# PFC_Method_V1_1.net
KiCad netlist of a schematic drawn in EAGLE
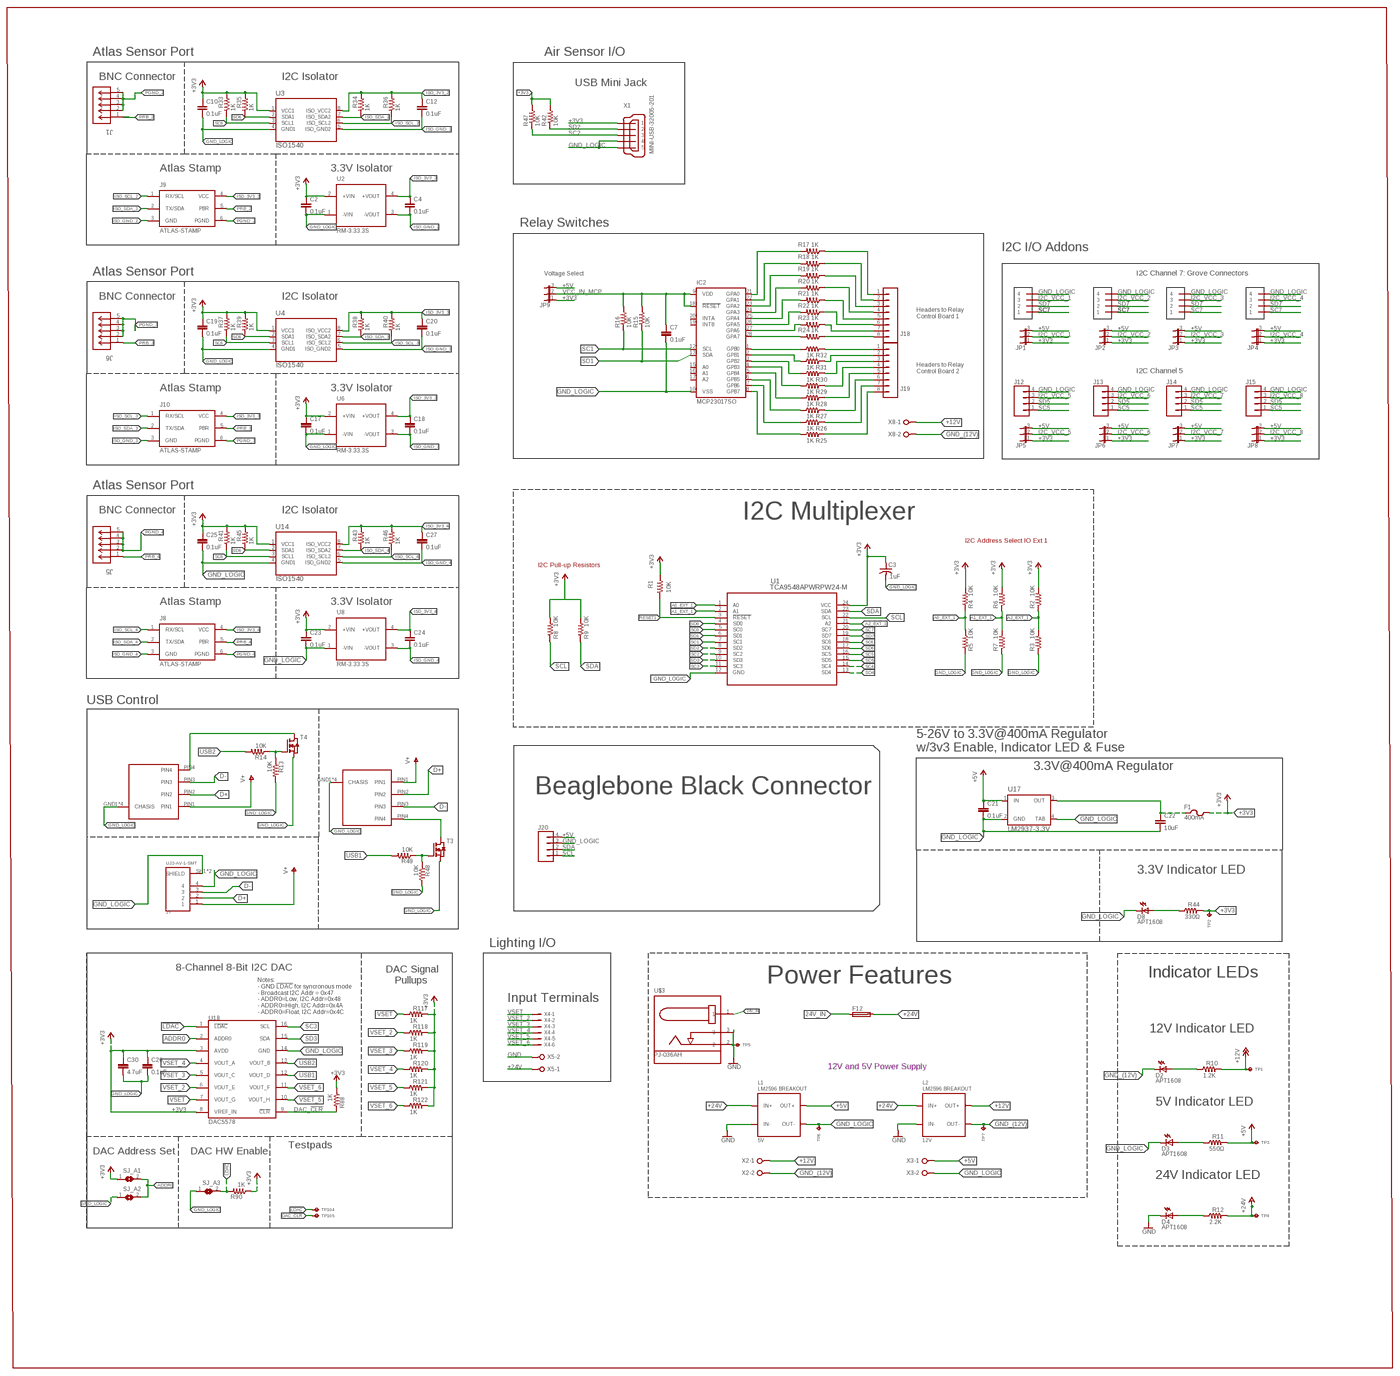
[diagram p0: schematic, sheet 1, overview]
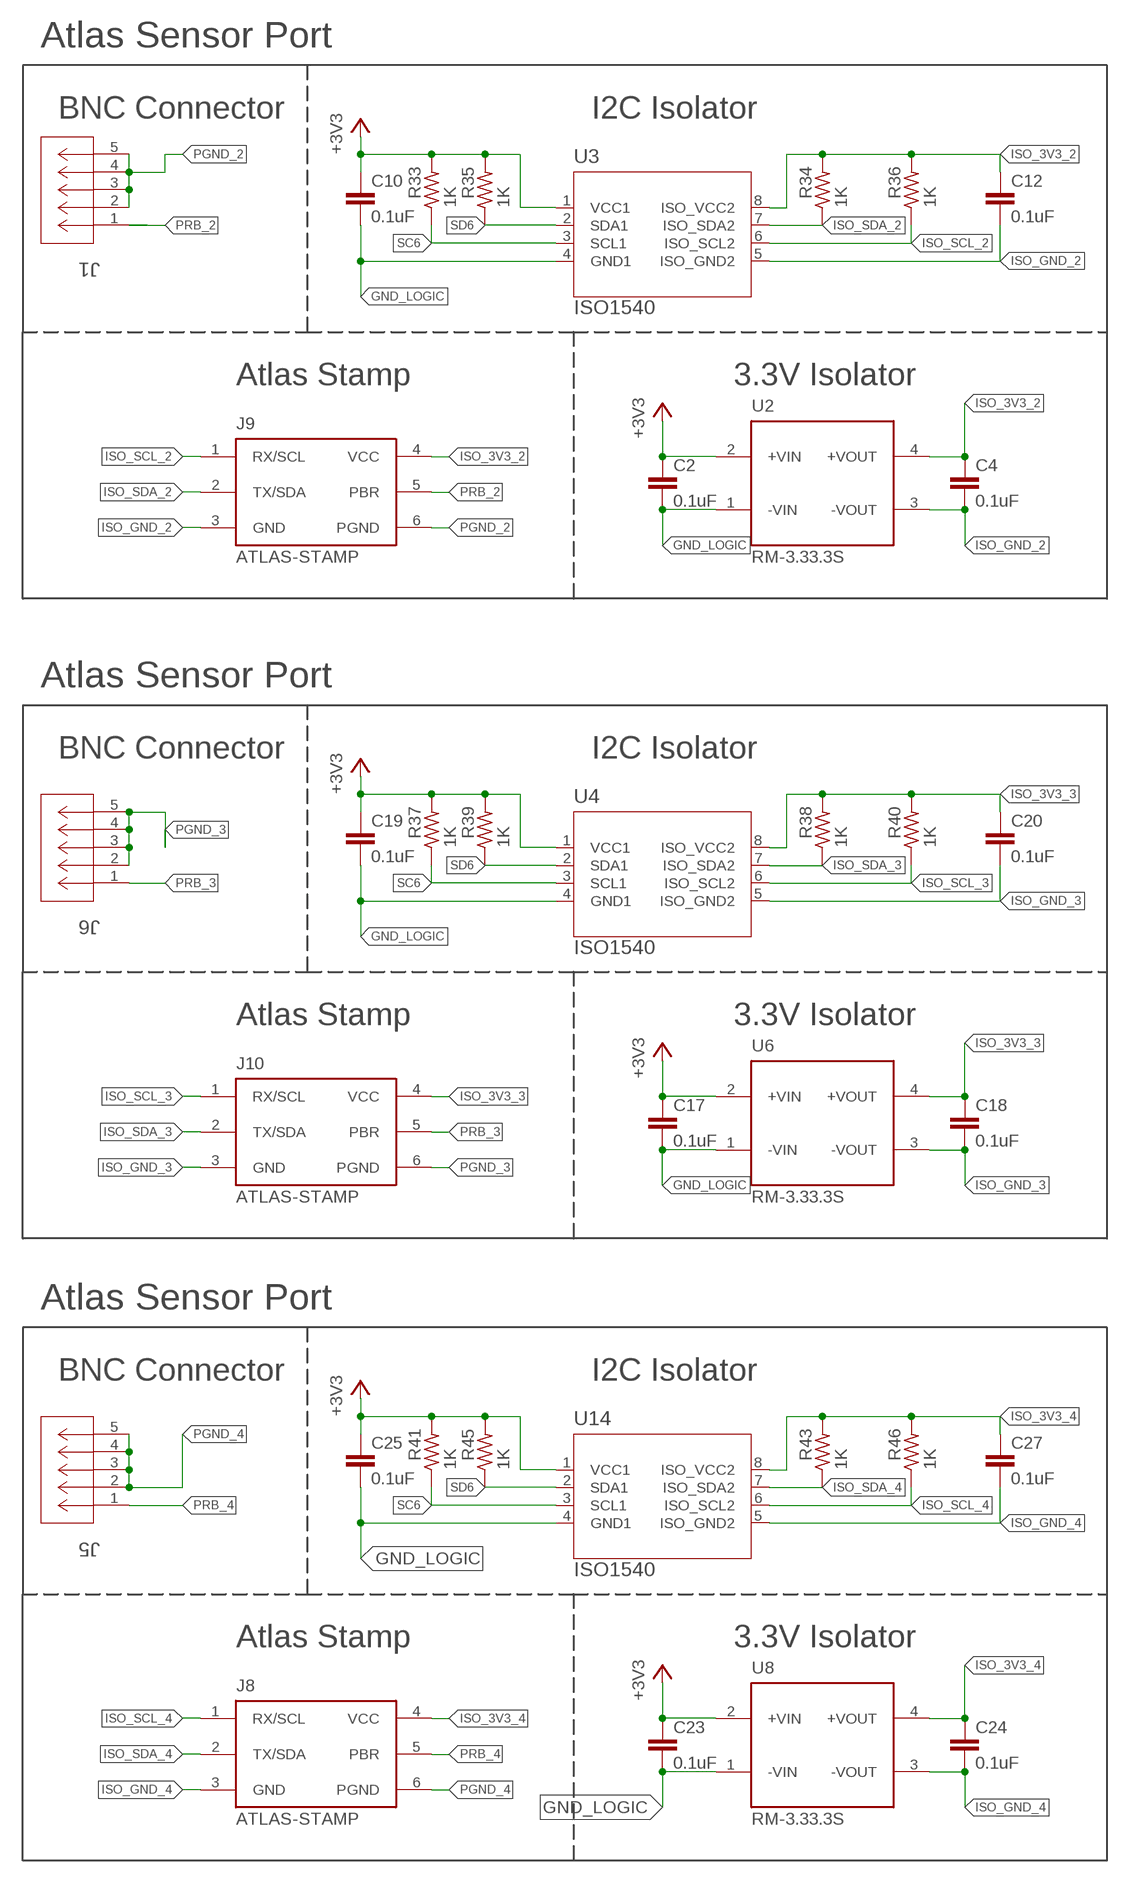
[diagram p1: schematic, sheet 1, part 1 of 4]
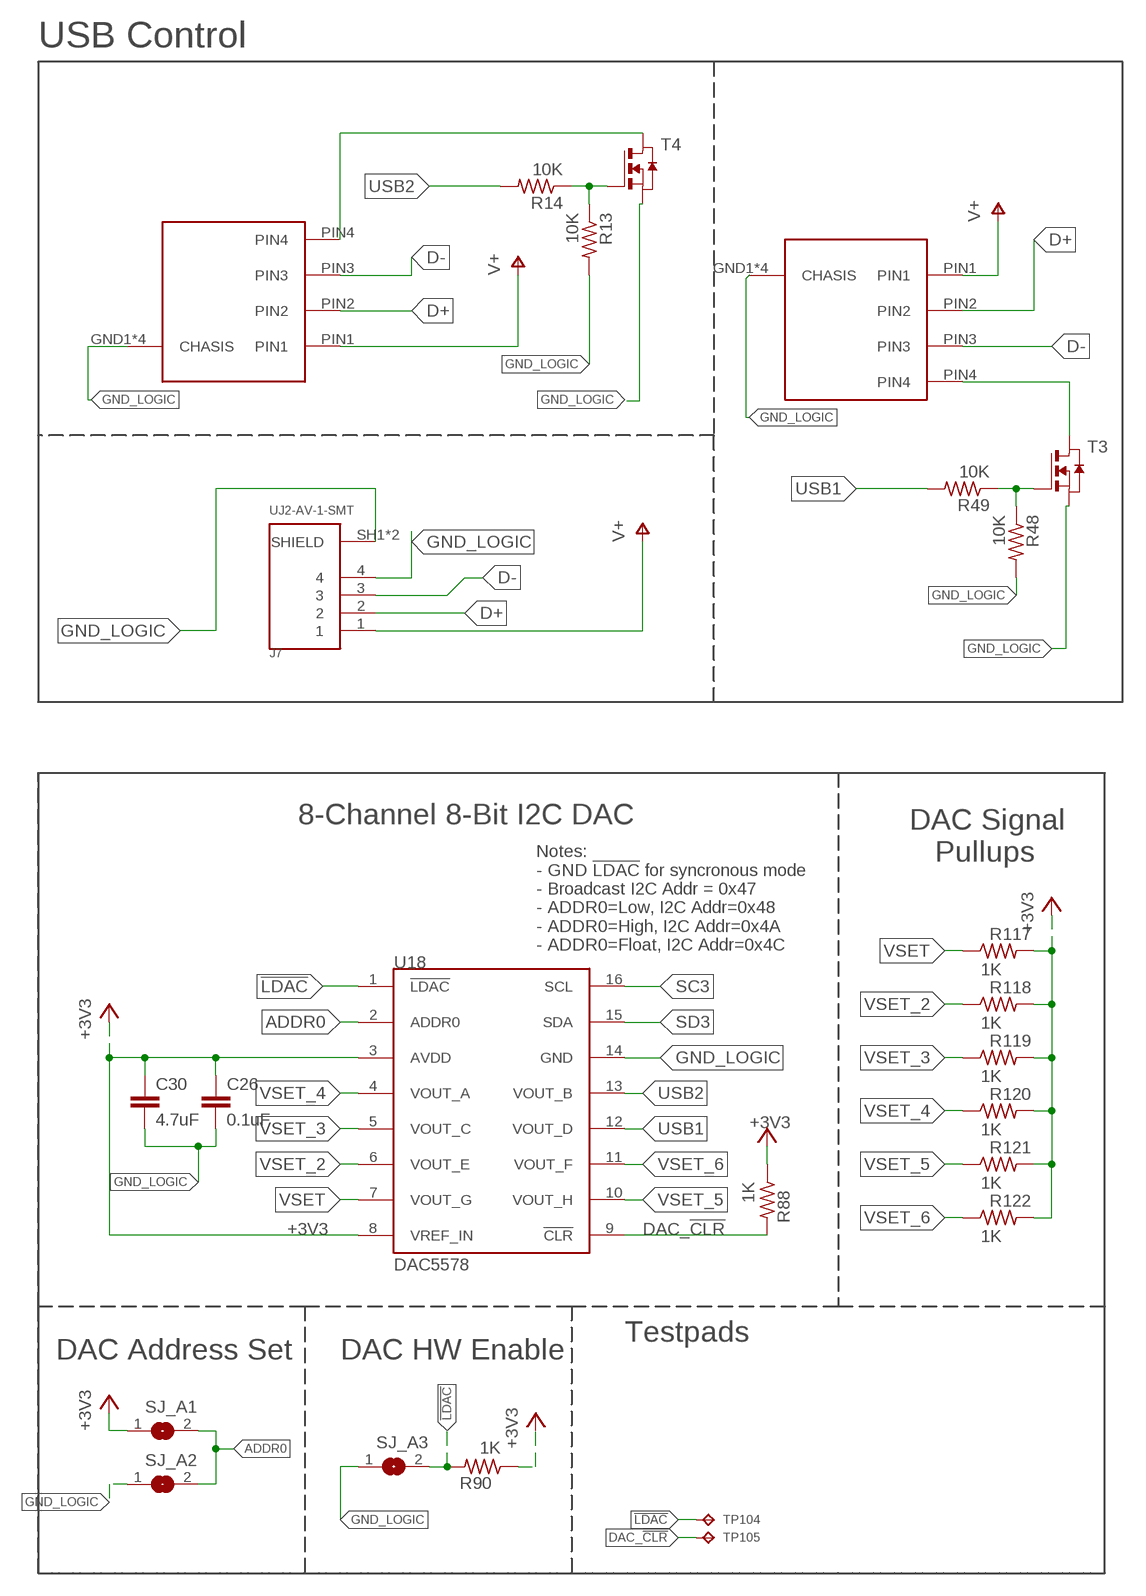
[diagram p2: schematic, sheet 1, part 2 of 4]
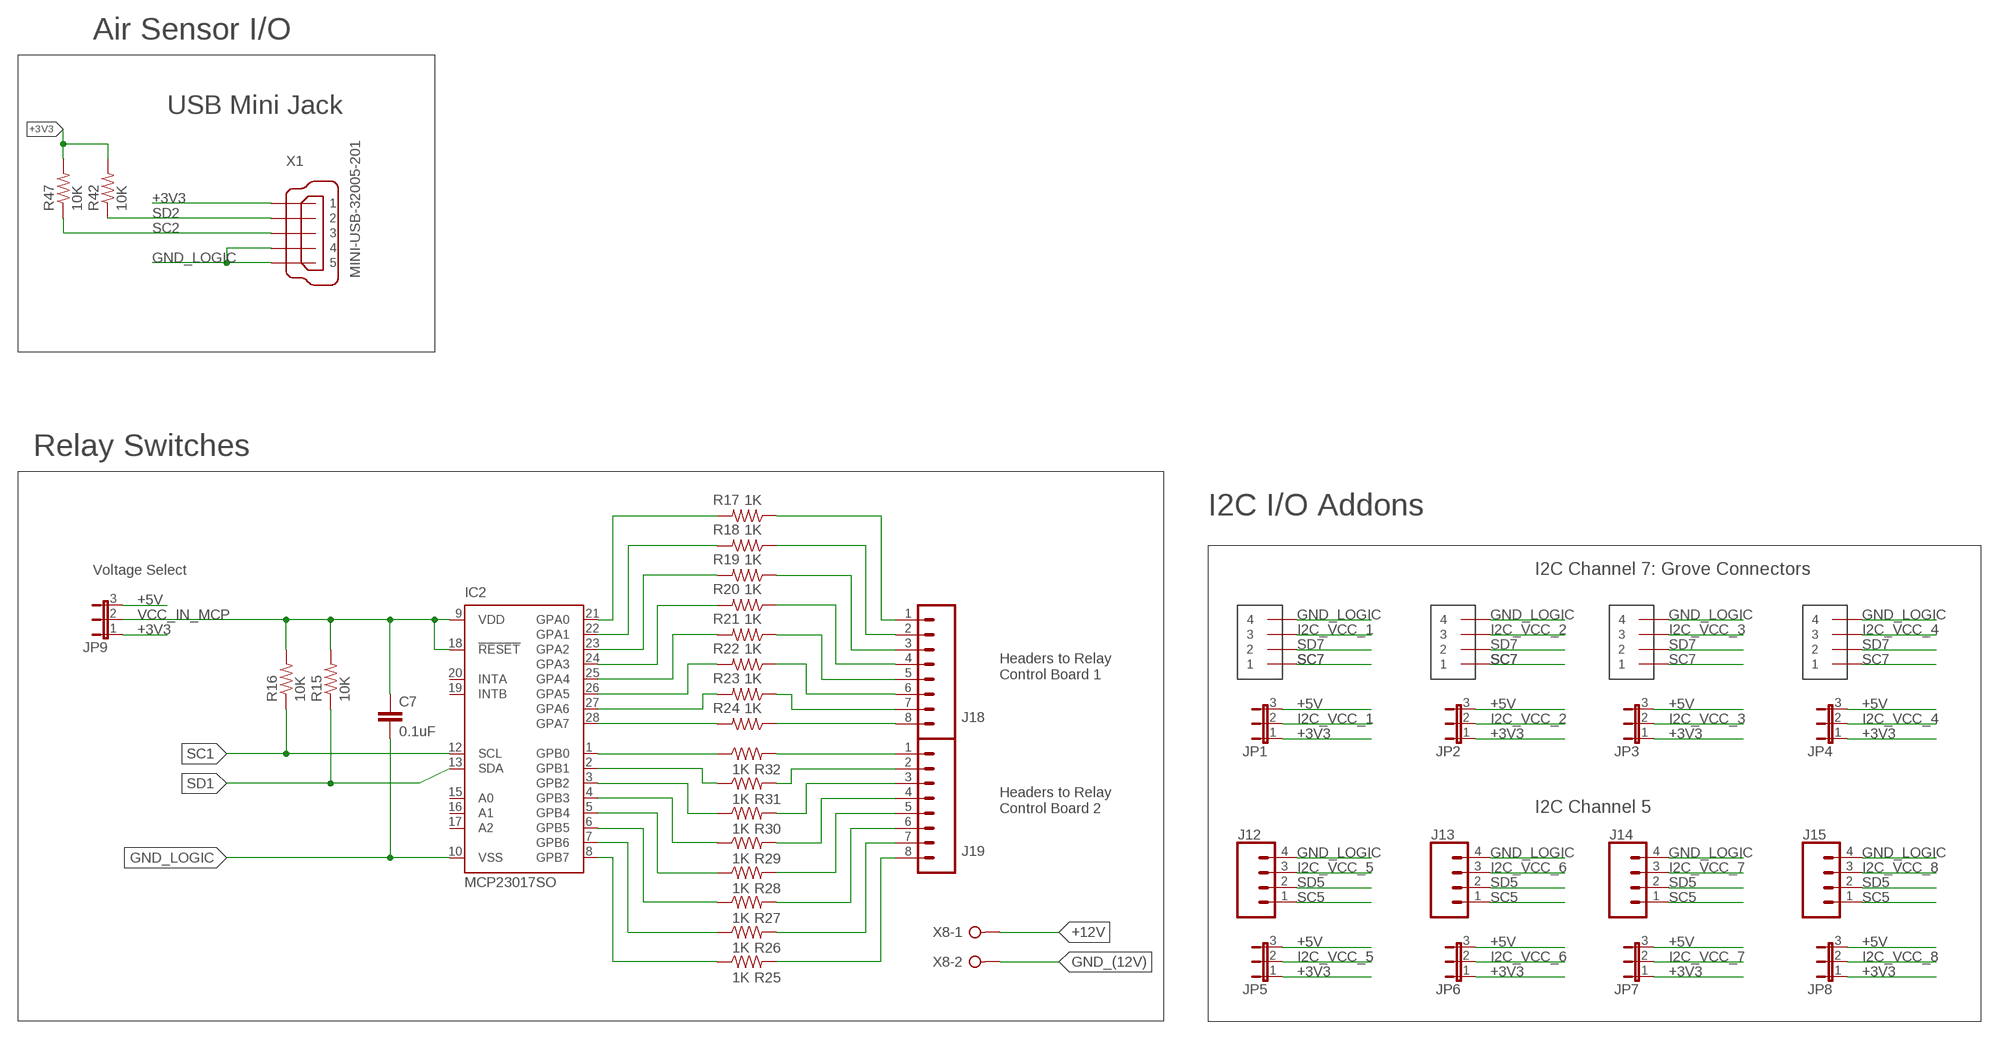
[diagram p3: schematic, sheet 1, part 3 of 4]
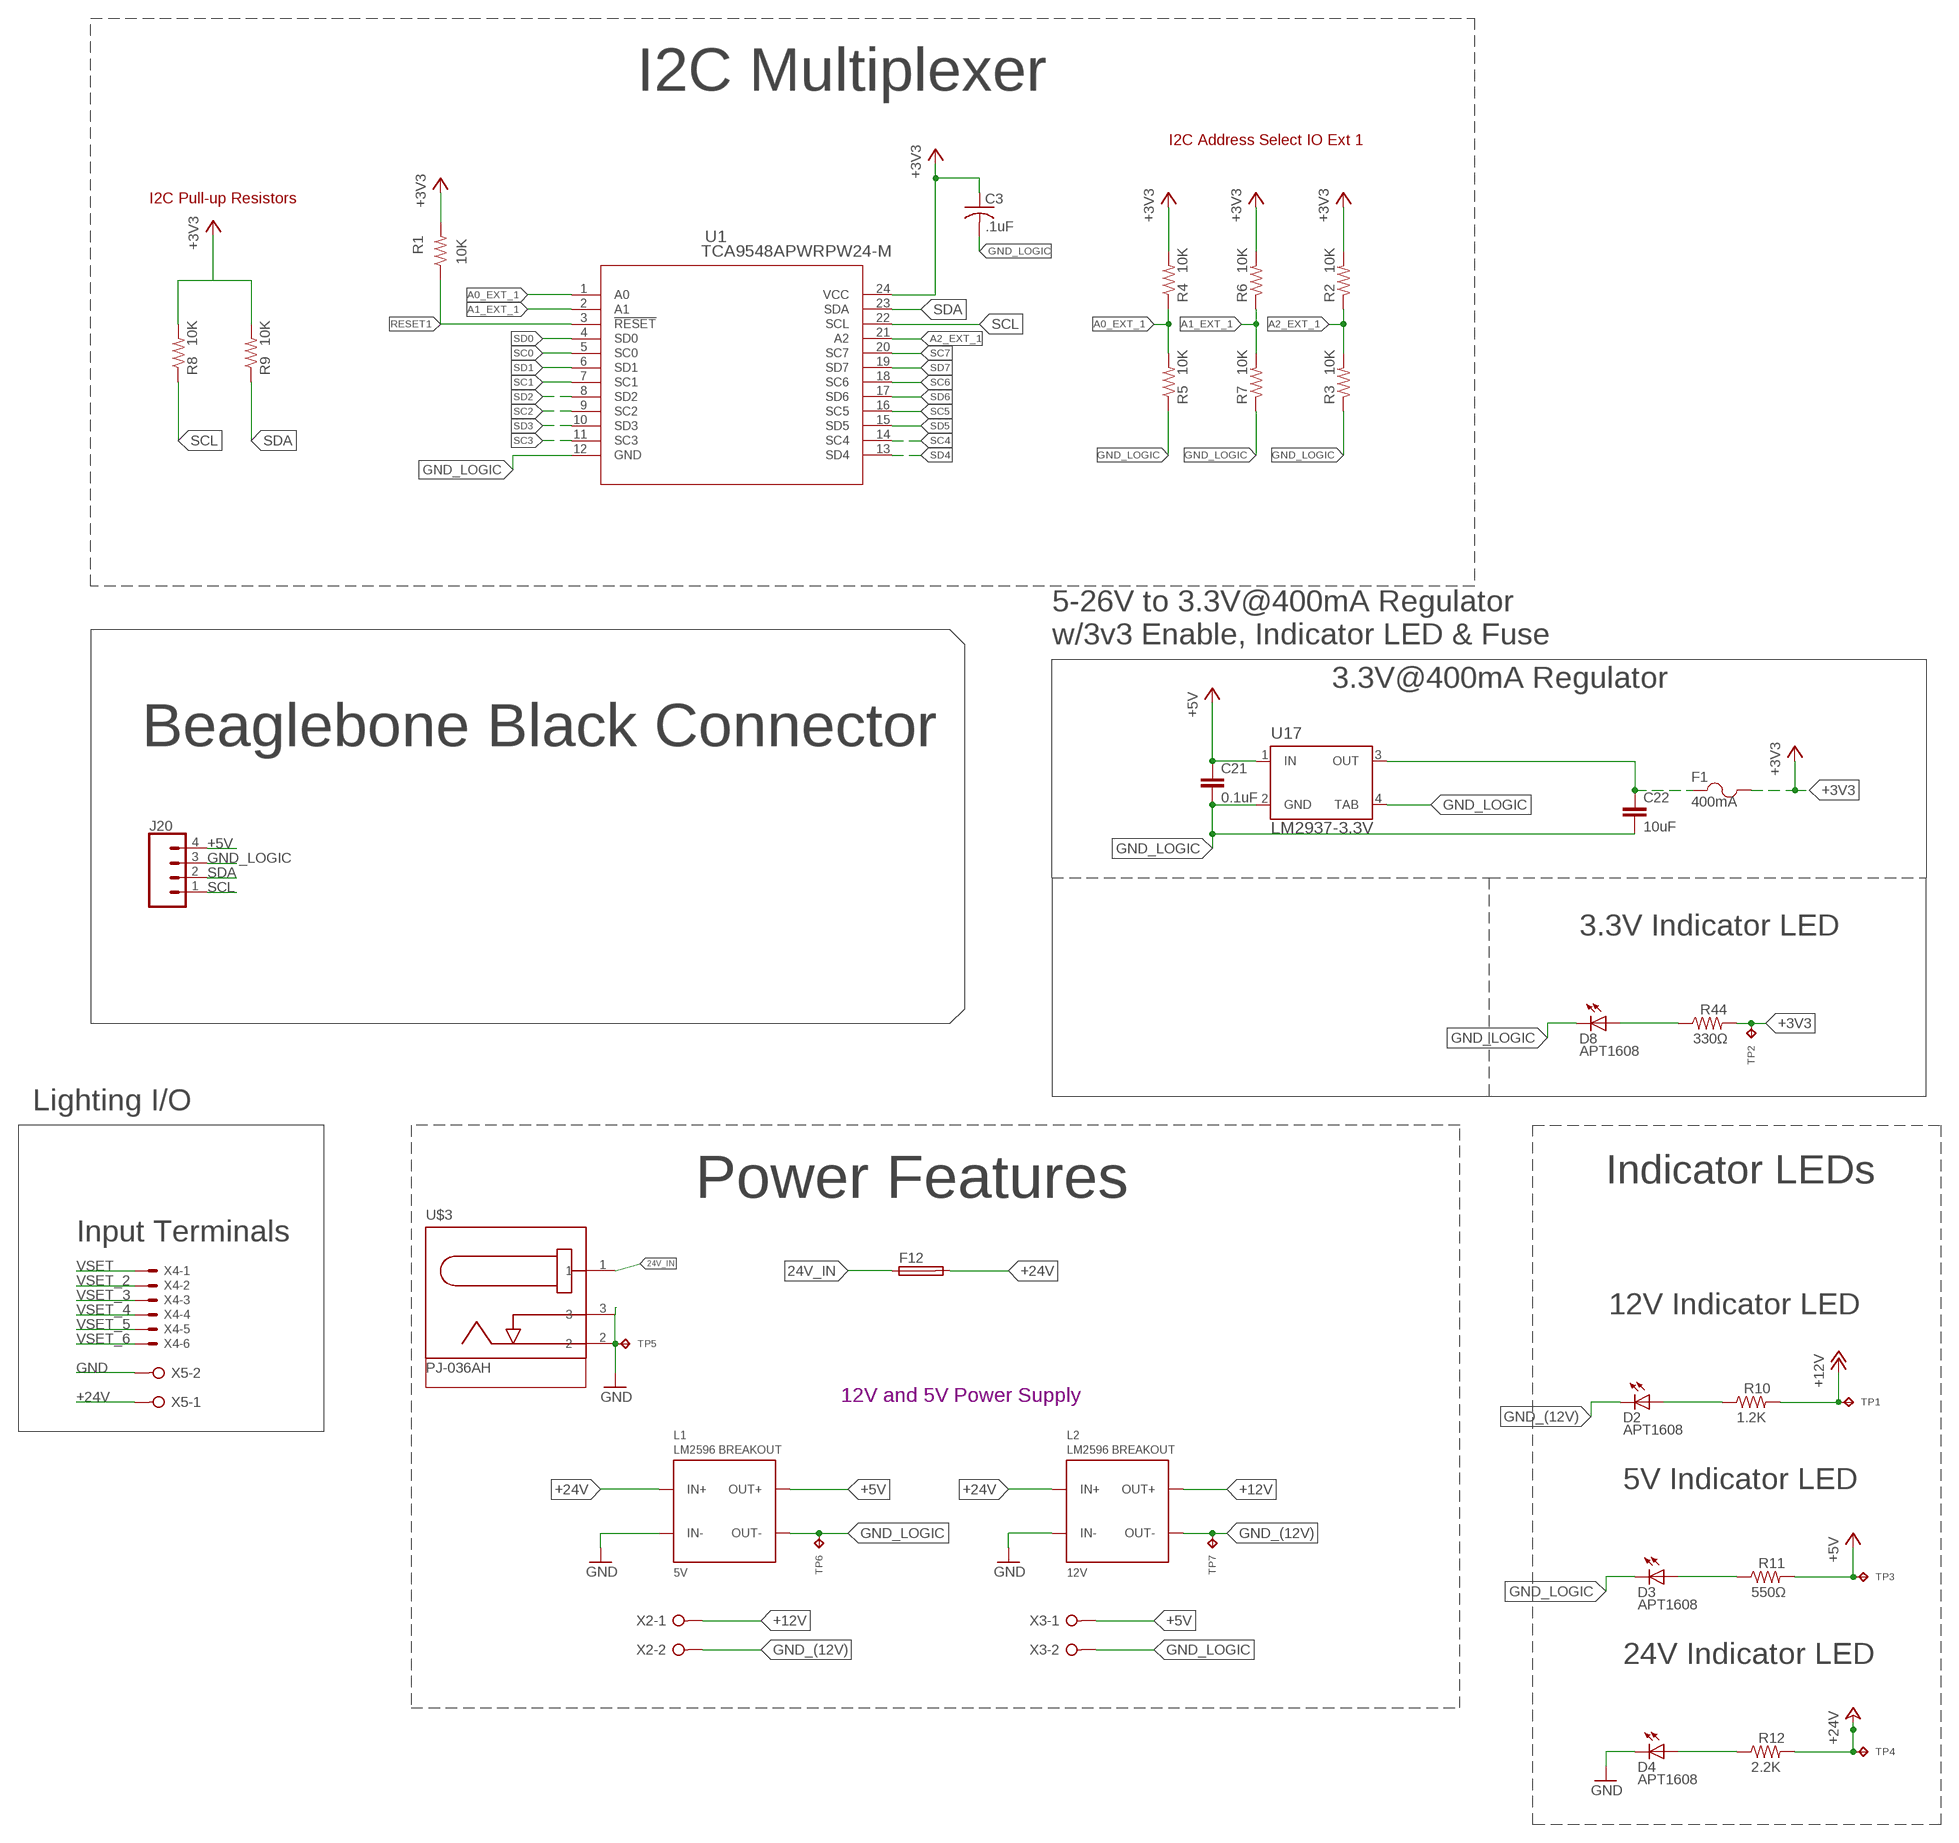
[diagram p4: schematic, sheet 1, part 4 of 4]

(export (version "E")
  (design (tool "Eeschema 10.0.6"))
  (components
    (comp (ref "C2")
      (value "0.1uF")
      (footprint "eagle-import:C0603")
      (fields (field (name "MANUFACTURER") "Kemet") (field (name "MPN") "C0603C104K5RACTU"))
      (libsource (lib "eagle-import") (part "0.1UF-C0603C104K5RACTU"))
    )
    (comp (ref "C3")
      (value ".1uF")
      (footprint "eagle-import:C0603@1")
      (libsource (lib "eagle-import") (part "C-USC0603"))
    )
    (comp (ref "C4")
      (value "0.1uF")
      (footprint "eagle-import:C0603")
      (fields (field (name "MANUFACTURER") "Kemet") (field (name "MPN") "C0603C104K5RACTU"))
      (libsource (lib "eagle-import") (part "0.1UF-C0603C104K5RACTU"))
    )
    (comp (ref "C7")
      (value "0.1uF")
      (footprint "eagle-import:C0603")
      (fields (field (name "MANUFACTURER") "Kemet") (field (name "MPN") "C0603C104K5RACTU"))
      (libsource (lib "eagle-import") (part "0.1UF-C0603C104K5RACTU"))
    )
    (comp (ref "C10")
      (value "0.1uF")
      (footprint "eagle-import:C0603")
      (fields (field (name "MANUFACTURER") "Kemet") (field (name "MPN") "C0603C104K5RACTU"))
      (libsource (lib "eagle-import") (part "0.1UF-C0603C104K5RACTU"))
    )
    (comp (ref "C12")
      (value "0.1uF")
      (footprint "eagle-import:C0603")
      (fields (field (name "MANUFACTURER") "Kemet") (field (name "MPN") "C0603C104K5RACTU"))
      (libsource (lib "eagle-import") (part "0.1UF-C0603C104K5RACTU"))
    )
    (comp (ref "C17")
      (value "0.1uF")
      (footprint "eagle-import:C0603")
      (fields (field (name "MANUFACTURER") "Kemet") (field (name "MPN") "C0603C104K5RACTU"))
      (libsource (lib "eagle-import") (part "0.1UF-C0603C104K5RACTU"))
    )
    (comp (ref "C18")
      (value "0.1uF")
      (footprint "eagle-import:C0603")
      (fields (field (name "MANUFACTURER") "Kemet") (field (name "MPN") "C0603C104K5RACTU"))
      (libsource (lib "eagle-import") (part "0.1UF-C0603C104K5RACTU"))
    )
    (comp (ref "C19")
      (value "0.1uF")
      (footprint "eagle-import:C0603")
      (fields (field (name "MANUFACTURER") "Kemet") (field (name "MPN") "C0603C104K5RACTU"))
      (libsource (lib "eagle-import") (part "0.1UF-C0603C104K5RACTU"))
    )
    (comp (ref "C20")
      (value "0.1uF")
      (footprint "eagle-import:C0603")
      (fields (field (name "MANUFACTURER") "Kemet") (field (name "MPN") "C0603C104K5RACTU"))
      (libsource (lib "eagle-import") (part "0.1UF-C0603C104K5RACTU"))
    )
    (comp (ref "C21")
      (value "0.1uF")
      (footprint "eagle-import:C0603")
      (fields (field (name "MANUFACTURER") "Kemet") (field (name "MPN") "C0603C104K5RACTU"))
      (libsource (lib "eagle-import") (part "0.1UF-C0603C104K5RACTU"))
    )
    (comp (ref "C22")
      (value "10uF")
      (footprint "eagle-import:C0805")
      (fields (field (name "MANUFACTURER") "Taiyo Yuden") (field (name "MPN") "GMK212BBJ106KG-T"))
      (libsource (lib "eagle-import") (part "10UF-GMK212BBJ106KG-T"))
    )
    (comp (ref "C23")
      (value "0.1uF")
      (footprint "eagle-import:C0603")
      (fields (field (name "MANUFACTURER") "Kemet") (field (name "MPN") "C0603C104K5RACTU"))
      (libsource (lib "eagle-import") (part "0.1UF-C0603C104K5RACTU"))
    )
    (comp (ref "C24")
      (value "0.1uF")
      (footprint "eagle-import:C0603")
      (fields (field (name "MANUFACTURER") "Kemet") (field (name "MPN") "C0603C104K5RACTU"))
      (libsource (lib "eagle-import") (part "0.1UF-C0603C104K5RACTU"))
    )
    (comp (ref "C25")
      (value "0.1uF")
      (footprint "eagle-import:C0603")
      (fields (field (name "MANUFACTURER") "Kemet") (field (name "MPN") "C0603C104K5RACTU"))
      (libsource (lib "eagle-import") (part "0.1UF-C0603C104K5RACTU"))
    )
    (comp (ref "C26")
      (value "0.1uF")
      (footprint "eagle-import:C0603")
      (fields (field (name "MANUFACTURER") "Kemet") (field (name "MPN") "C0603C104K5RACTU"))
      (libsource (lib "eagle-import") (part "0.1UF-C0603C104K5RACTU"))
    )
    (comp (ref "C27")
      (value "0.1uF")
      (footprint "eagle-import:C0603")
      (fields (field (name "MANUFACTURER") "Kemet") (field (name "MPN") "C0603C104K5RACTU"))
      (libsource (lib "eagle-import") (part "0.1UF-C0603C104K5RACTU"))
    )
    (comp (ref "C30")
      (value "4.7uF")
      (footprint "eagle-import:C0805")
      (fields (field (name "MANUFACTURER") "Samsung") (field (name "MPN") "CL21A475KBQNNNE"))
      (libsource (lib "eagle-import") (part "4.7UF-CL21A475KBQNNNE"))
    )
    (comp (ref "D2")
      (value "APT1608")
      (footprint "eagle-import:CHIPLED_0603")
      (fields (field (name "MANUFACTURER") "Kingbright") (field (name "MPN") "APT1608CGCK"))
      (libsource (lib "eagle-import") (part "APT1608CGCK"))
    )
    (comp (ref "D3")
      (value "APT1608")
      (footprint "eagle-import:CHIPLED_0603")
      (fields (field (name "MANUFACTURER") "Kingbright") (field (name "MPN") "APT1608CGCK"))
      (libsource (lib "eagle-import") (part "APT1608CGCK"))
    )
    (comp (ref "D4")
      (value "APT1608")
      (footprint "eagle-import:CHIPLED_0603")
      (fields (field (name "MANUFACTURER") "Kingbright") (field (name "MPN") "APT1608CGCK"))
      (libsource (lib "eagle-import") (part "APT1608CGCK"))
    )
    (comp (ref "D8")
      (value "APT1608")
      (footprint "eagle-import:CHIPLED_0603")
      (fields (field (name "MANUFACTURER") "Kingbright") (field (name "MPN") "APT1608CGCK"))
      (libsource (lib "eagle-import") (part "APT1608CGCK"))
    )
    (comp (ref "F1")
      (value "400mA")
      (footprint "eagle-import:0603")
      (fields (field (name "MANUFACTURER") "Littlefuse Inc.") (field (name "MPN") "0448.400MR"))
      (libsource (lib "eagle-import") (part "0438.375WR"))
    )
    (comp (ref "F12")
      (value "GSH15")
      (footprint "eagle-import:GSH15")
      (fields (field (name "MPN") "64900001039"))
      (libsource (lib "eagle-import") (part "GSH15"))
    )
    (comp (ref "IC2")
      (value "MCP23017SO")
      (footprint "eagle-import:SO28W")
      (fields (field (name "MF") "MICROCHIP") (field (name "MPN") "MCP23017-E/SO"))
      (libsource (lib "eagle-import") (part "MCP23017SO"))
    )
    (comp (ref "J1")
      (value "5-1634503-1")
      (footprint "eagle-import:CONN5_5-1634503-1")
      (fields (field (name "MANUFACTURER_PART_NUMBER") "516345031"))
      (libsource (lib "eagle-import") (part "5-1634503-1"))
    )
    (comp (ref "J2")
      (value "GROVE_4PIN_CONNECTOR")
      (footprint "eagle-import:GROVE_4PIN_CONNECTOR")
      (libsource (lib "eagle-import") (part "GROVE_4PIN_CONNECTOR"))
    )
    (comp (ref "J3")
      (value "GROVE_4PIN_CONNECTOR")
      (footprint "eagle-import:GROVE_4PIN_CONNECTOR")
      (libsource (lib "eagle-import") (part "GROVE_4PIN_CONNECTOR"))
    )
    (comp (ref "J5")
      (value "5-1634503-1")
      (footprint "eagle-import:CONN5_5-1634503-1")
      (fields (field (name "MANUFACTURER_PART_NUMBER") "516345031"))
      (libsource (lib "eagle-import") (part "5-1634503-1"))
    )
    (comp (ref "J6")
      (value "5-1634503-1")
      (footprint "eagle-import:CONN5_5-1634503-1")
      (fields (field (name "MANUFACTURER_PART_NUMBER") "516345031"))
      (libsource (lib "eagle-import") (part "5-1634503-1"))
    )
    (comp (ref "J7")
      (value "UJ2-AV-1-SMT")
      (footprint "eagle-import:CUI_UJ2-AV-1-SMT")
      (fields (field (name "MANUFACTURER") "CUI INC"))
      (libsource (lib "eagle-import") (part "UJ2-AV-1-SMT"))
    )
    (comp (ref "J8")
      (value "ATLAS-STAMP")
      (footprint "eagle-import:ATLAS-STAMP")
      (libsource (lib "eagle-import") (part "ATLAS-STAMP"))
    )
    (comp (ref "J9")
      (value "ATLAS-STAMP")
      (footprint "eagle-import:ATLAS-STAMP")
      (libsource (lib "eagle-import") (part "ATLAS-STAMP"))
    )
    (comp (ref "J10")
      (value "ATLAS-STAMP")
      (footprint "eagle-import:ATLAS-STAMP")
      (libsource (lib "eagle-import") (part "ATLAS-STAMP"))
    )
    (comp (ref "J12")
      (value "CONN_04")
      (footprint "eagle-import:1X04")
      (libsource (lib "eagle-import") (part "CONN_04"))
    )
    (comp (ref "J13")
      (value "CONN_04")
      (footprint "eagle-import:1X04")
      (libsource (lib "eagle-import") (part "CONN_04"))
    )
    (comp (ref "J14")
      (value "CONN_04")
      (footprint "eagle-import:1X04")
      (libsource (lib "eagle-import") (part "CONN_04"))
    )
    (comp (ref "J15")
      (value "CONN_04")
      (footprint "eagle-import:1X04")
      (libsource (lib "eagle-import") (part "CONN_04"))
    )
    (comp (ref "J16")
      (value "GROVE_4PIN_CONNECTOR")
      (footprint "eagle-import:GROVE_4PIN_CONNECTOR")
      (libsource (lib "eagle-import") (part "GROVE_4PIN_CONNECTOR"))
    )
    (comp (ref "J17")
      (value "GROVE_4PIN_CONNECTOR")
      (footprint "eagle-import:GROVE_4PIN_CONNECTOR")
      (libsource (lib "eagle-import") (part "GROVE_4PIN_CONNECTOR"))
    )
    (comp (ref "J18")
      (value "CONN_08\"")
      (footprint "eagle-import:1X08")
      (libsource (lib "eagle-import") (part "CONN_08{dblquote}"))
    )
    (comp (ref "J19")
      (value "CONN_08\"")
      (footprint "eagle-import:1X08")
      (libsource (lib "eagle-import") (part "CONN_08{dblquote}"))
    )
    (comp (ref "J20")
      (value "CONN_04")
      (footprint "eagle-import:1X04")
      (libsource (lib "eagle-import") (part "CONN_04"))
    )
    (comp (ref "JP1")
      (value "JP2E")
      (footprint "eagle-import:JP2")
      (libsource (lib "eagle-import") (part "JP2E"))
    )
    (comp (ref "JP2")
      (value "JP2E")
      (footprint "eagle-import:JP2")
      (libsource (lib "eagle-import") (part "JP2E"))
    )
    (comp (ref "JP3")
      (value "JP2E")
      (footprint "eagle-import:JP2")
      (libsource (lib "eagle-import") (part "JP2E"))
    )
    (comp (ref "JP4")
      (value "JP2E")
      (footprint "eagle-import:JP2")
      (libsource (lib "eagle-import") (part "JP2E"))
    )
    (comp (ref "JP5")
      (value "JP2E")
      (footprint "eagle-import:JP2")
      (libsource (lib "eagle-import") (part "JP2E"))
    )
    (comp (ref "JP6")
      (value "JP2E")
      (footprint "eagle-import:JP2")
      (libsource (lib "eagle-import") (part "JP2E"))
    )
    (comp (ref "JP7")
      (value "JP2E")
      (footprint "eagle-import:JP2")
      (libsource (lib "eagle-import") (part "JP2E"))
    )
    (comp (ref "JP8")
      (value "JP2E")
      (footprint "eagle-import:JP2")
      (libsource (lib "eagle-import") (part "JP2E"))
    )
    (comp (ref "JP9")
      (value "JP2E")
      (footprint "eagle-import:JP2")
      (libsource (lib "eagle-import") (part "JP2E"))
    )
    (comp (ref "L1")
      (value "5V")
      (footprint "eagle-import:LM2596")
      (libsource (lib "eagle-import") (part "LM2596_BREAKOUT"))
    )
    (comp (ref "L2")
      (value "12V")
      (footprint "eagle-import:LM2596")
      (libsource (lib "eagle-import") (part "LM2596_BREAKOUT"))
    )
    (comp (ref "R1")
      (value "10K")
      (footprint "eagle-import:R0603")
      (libsource (lib "eagle-import") (part "R-US_R0603"))
    )
    (comp (ref "R2")
      (value "10K")
      (footprint "eagle-import:0603-RES")
      (libsource (lib "eagle-import") (part "10KOHM-1/10W-1%(0603)0603"))
    )
    (comp (ref "R3")
      (value "10K")
      (footprint "eagle-import:0603-RES")
      (libsource (lib "eagle-import") (part "10KOHM-1/10W-1%(0603)0603"))
    )
    (comp (ref "R4")
      (value "10K")
      (footprint "eagle-import:0603-RES")
      (libsource (lib "eagle-import") (part "10KOHM-1/10W-1%(0603)0603"))
    )
    (comp (ref "R5")
      (value "10K")
      (footprint "eagle-import:0603-RES")
      (libsource (lib "eagle-import") (part "10KOHM-1/10W-1%(0603)0603"))
    )
    (comp (ref "R6")
      (value "10K")
      (footprint "eagle-import:0603-RES")
      (libsource (lib "eagle-import") (part "10KOHM-1/10W-1%(0603)0603"))
    )
    (comp (ref "R7")
      (value "10K")
      (footprint "eagle-import:0603-RES")
      (libsource (lib "eagle-import") (part "10KOHM-1/10W-1%(0603)0603"))
    )
    (comp (ref "R8")
      (value "10K")
      (footprint "eagle-import:0603-RES")
      (libsource (lib "eagle-import") (part "10KOHM-1/10W-1%(0603)0603"))
    )
    (comp (ref "R9")
      (value "10K")
      (footprint "eagle-import:0603-RES")
      (libsource (lib "eagle-import") (part "10KOHM-1/10W-1%(0603)0603"))
    )
    (comp (ref "R10")
      (value "1.2K")
      (footprint "eagle-import:RC0603N")
      (fields (field (name "MANUFACTURER") "Yageo") (field (name "MPN") "RC0603JR-07100RL"))
      (libsource (lib "eagle-import") (part "100OHM-RC0603JR-07100RL"))
    )
    (comp (ref "R11")
      (value "550Ω")
      (footprint "eagle-import:RC0603N")
      (fields (field (name "MANUFACTURER") "Yageo") (field (name "MPN") "RC0603JR-07100RL"))
      (libsource (lib "eagle-import") (part "100OHM-RC0603JR-07100RL"))
    )
    (comp (ref "R12")
      (value "2.2K")
      (footprint "eagle-import:RC0603N")
      (fields (field (name "MANUFACTURER") "Yageo") (field (name "MPN") "RC0603JR-07100RL"))
      (libsource (lib "eagle-import") (part "100OHM-RC0603JR-07100RL"))
    )
    (comp (ref "R13")
      (value "10K")
      (footprint "eagle-import:R0805W")
      (libsource (lib "eagle-import") (part "R-US_R0805W"))
    )
    (comp (ref "R14")
      (value "10K")
      (footprint "eagle-import:R0805W")
      (libsource (lib "eagle-import") (part "R-US_R0805W"))
    )
    (comp (ref "R15")
      (value "10K")
      (footprint "eagle-import:R0603")
      (libsource (lib "eagle-import") (part "R-US_R0603"))
    )
    (comp (ref "R16")
      (value "10K")
      (footprint "eagle-import:R0603")
      (libsource (lib "eagle-import") (part "R-US_R0603"))
    )
    (comp (ref "R17")
      (value "1K")
      (footprint "eagle-import:RC0603N")
      (fields (field (name "MANUFACTURER") "Panasonic") (field (name "MPN") "P20283CT-ND"))
      (libsource (lib "eagle-import") (part "1K-ERJ-PB3D1001V"))
    )
    (comp (ref "R18")
      (value "1K")
      (footprint "eagle-import:RC0603N")
      (fields (field (name "MANUFACTURER") "Panasonic") (field (name "MPN") "P20283CT-ND"))
      (libsource (lib "eagle-import") (part "1K-ERJ-PB3D1001V"))
    )
    (comp (ref "R19")
      (value "1K")
      (footprint "eagle-import:RC0603N")
      (fields (field (name "MANUFACTURER") "Panasonic") (field (name "MPN") "P20283CT-ND"))
      (libsource (lib "eagle-import") (part "1K-ERJ-PB3D1001V"))
    )
    (comp (ref "R20")
      (value "1K")
      (footprint "eagle-import:RC0603N")
      (fields (field (name "MANUFACTURER") "Panasonic") (field (name "MPN") "P20283CT-ND"))
      (libsource (lib "eagle-import") (part "1K-ERJ-PB3D1001V"))
    )
    (comp (ref "R21")
      (value "1K")
      (footprint "eagle-import:RC0603N")
      (fields (field (name "MANUFACTURER") "Panasonic") (field (name "MPN") "P20283CT-ND"))
      (libsource (lib "eagle-import") (part "1K-ERJ-PB3D1001V"))
    )
    (comp (ref "R22")
      (value "1K")
      (footprint "eagle-import:RC0603N")
      (fields (field (name "MANUFACTURER") "Panasonic") (field (name "MPN") "P20283CT-ND"))
      (libsource (lib "eagle-import") (part "1K-ERJ-PB3D1001V"))
    )
    (comp (ref "R23")
      (value "1K")
      (footprint "eagle-import:RC0603N")
      (fields (field (name "MANUFACTURER") "Panasonic") (field (name "MPN") "P20283CT-ND"))
      (libsource (lib "eagle-import") (part "1K-ERJ-PB3D1001V"))
    )
    (comp (ref "R24")
      (value "1K")
      (footprint "eagle-import:RC0603N")
      (fields (field (name "MANUFACTURER") "Panasonic") (field (name "MPN") "P20283CT-ND"))
      (libsource (lib "eagle-import") (part "1K-ERJ-PB3D1001V"))
    )
    (comp (ref "R25")
      (value "1K")
      (footprint "eagle-import:RC0603N")
      (fields (field (name "MANUFACTURER") "Panasonic") (field (name "MPN") "P20283CT-ND"))
      (libsource (lib "eagle-import") (part "1K-ERJ-PB3D1001V"))
    )
    (comp (ref "R26")
      (value "1K")
      (footprint "eagle-import:RC0603N")
      (fields (field (name "MANUFACTURER") "Panasonic") (field (name "MPN") "P20283CT-ND"))
      (libsource (lib "eagle-import") (part "1K-ERJ-PB3D1001V"))
    )
    (comp (ref "R27")
      (value "1K")
      (footprint "eagle-import:RC0603N")
      (fields (field (name "MANUFACTURER") "Panasonic") (field (name "MPN") "P20283CT-ND"))
      (libsource (lib "eagle-import") (part "1K-ERJ-PB3D1001V"))
    )
    (comp (ref "R28")
      (value "1K")
      (footprint "eagle-import:RC0603N")
      (fields (field (name "MANUFACTURER") "Panasonic") (field (name "MPN") "P20283CT-ND"))
      (libsource (lib "eagle-import") (part "1K-ERJ-PB3D1001V"))
    )
    (comp (ref "R29")
      (value "1K")
      (footprint "eagle-import:RC0603N")
      (fields (field (name "MANUFACTURER") "Panasonic") (field (name "MPN") "P20283CT-ND"))
      (libsource (lib "eagle-import") (part "1K-ERJ-PB3D1001V"))
    )
    (comp (ref "R30")
      (value "1K")
      (footprint "eagle-import:RC0603N")
      (fields (field (name "MANUFACTURER") "Panasonic") (field (name "MPN") "P20283CT-ND"))
      (libsource (lib "eagle-import") (part "1K-ERJ-PB3D1001V"))
    )
    (comp (ref "R31")
      (value "1K")
      (footprint "eagle-import:RC0603N")
      (fields (field (name "MANUFACTURER") "Panasonic") (field (name "MPN") "P20283CT-ND"))
      (libsource (lib "eagle-import") (part "1K-ERJ-PB3D1001V"))
    )
    (comp (ref "R32")
      (value "1K")
      (footprint "eagle-import:RC0603N")
      (fields (field (name "MANUFACTURER") "Panasonic") (field (name "MPN") "P20283CT-ND"))
      (libsource (lib "eagle-import") (part "1K-ERJ-PB3D1001V"))
    )
    (comp (ref "R33")
      (value "1K")
      (footprint "eagle-import:RC0603N")
      (fields (field (name "MANUFACTURER") "Panasonic") (field (name "MPN") "P20283CT-ND"))
      (libsource (lib "eagle-import") (part "1K-ERJ-PB3D1001V"))
    )
    (comp (ref "R34")
      (value "1K")
      (footprint "eagle-import:RC0603N")
      (fields (field (name "MANUFACTURER") "Panasonic") (field (name "MPN") "P20283CT-ND"))
      (libsource (lib "eagle-import") (part "1K-ERJ-PB3D1001V"))
    )
    (comp (ref "R35")
      (value "1K")
      (footprint "eagle-import:RC0603N")
      (fields (field (name "MANUFACTURER") "Panasonic") (field (name "MPN") "P20283CT-ND"))
      (libsource (lib "eagle-import") (part "1K-ERJ-PB3D1001V"))
    )
    (comp (ref "R36")
      (value "1K")
      (footprint "eagle-import:RC0603N")
      (fields (field (name "MANUFACTURER") "Panasonic") (field (name "MPN") "P20283CT-ND"))
      (libsource (lib "eagle-import") (part "1K-ERJ-PB3D1001V"))
    )
    (comp (ref "R37")
      (value "1K")
      (footprint "eagle-import:RC0603N")
      (fields (field (name "MANUFACTURER") "Panasonic") (field (name "MPN") "P20283CT-ND"))
      (libsource (lib "eagle-import") (part "1K-ERJ-PB3D1001V"))
    )
    (comp (ref "R38")
      (value "1K")
      (footprint "eagle-import:RC0603N")
      (fields (field (name "MANUFACTURER") "Panasonic") (field (name "MPN") "P20283CT-ND"))
      (libsource (lib "eagle-import") (part "1K-ERJ-PB3D1001V"))
    )
    (comp (ref "R39")
      (value "1K")
      (footprint "eagle-import:RC0603N")
      (fields (field (name "MANUFACTURER") "Panasonic") (field (name "MPN") "P20283CT-ND"))
      (libsource (lib "eagle-import") (part "1K-ERJ-PB3D1001V"))
    )
    (comp (ref "R40")
      (value "1K")
      (footprint "eagle-import:RC0603N")
      (fields (field (name "MANUFACTURER") "Panasonic") (field (name "MPN") "P20283CT-ND"))
      (libsource (lib "eagle-import") (part "1K-ERJ-PB3D1001V"))
    )
    (comp (ref "R41")
      (value "1K")
      (footprint "eagle-import:RC0603N")
      (fields (field (name "MANUFACTURER") "Panasonic") (field (name "MPN") "P20283CT-ND"))
      (libsource (lib "eagle-import") (part "1K-ERJ-PB3D1001V"))
    )
    (comp (ref "R42")
      (value "10K")
      (footprint "eagle-import:R0603")
      (libsource (lib "eagle-import") (part "R-US_R0603"))
    )
    (comp (ref "R43")
      (value "1K")
      (footprint "eagle-import:RC0603N")
      (fields (field (name "MANUFACTURER") "Panasonic") (field (name "MPN") "P20283CT-ND"))
      (libsource (lib "eagle-import") (part "1K-ERJ-PB3D1001V"))
    )
    (comp (ref "R44")
      (value "330Ω")
      (footprint "eagle-import:RC0603N")
      (fields (field (name "MANUFACTURER") "Yageo") (field (name "MPN") "RC0603JR-07100RL"))
      (libsource (lib "eagle-import") (part "100OHM-RC0603JR-07100RL"))
    )
    (comp (ref "R45")
      (value "1K")
      (footprint "eagle-import:RC0603N")
      (fields (field (name "MANUFACTURER") "Panasonic") (field (name "MPN") "P20283CT-ND"))
      (libsource (lib "eagle-import") (part "1K-ERJ-PB3D1001V"))
    )
    (comp (ref "R46")
      (value "1K")
      (footprint "eagle-import:RC0603N")
      (fields (field (name "MANUFACTURER") "Panasonic") (field (name "MPN") "P20283CT-ND"))
      (libsource (lib "eagle-import") (part "1K-ERJ-PB3D1001V"))
    )
    (comp (ref "R47")
      (value "10K")
      (footprint "eagle-import:R0603")
      (libsource (lib "eagle-import") (part "R-US_R0603"))
    )
    (comp (ref "R48")
      (value "10K")
      (footprint "eagle-import:R0805W")
      (libsource (lib "eagle-import") (part "R-US_R0805W"))
    )
    (comp (ref "R49")
      (value "10K")
      (footprint "eagle-import:R0805W")
      (libsource (lib "eagle-import") (part "R-US_R0805W"))
    )
    (comp (ref "R88")
      (value "1K")
      (footprint "eagle-import:RC0603N")
      (fields (field (name "MANUFACTURER") "Panasonic") (field (name "MPN") "P20283CT-ND"))
      (libsource (lib "eagle-import") (part "1K-ERJ-PB3D1001V"))
    )
    (comp (ref "R90")
      (value "1K")
      (footprint "eagle-import:RC0603N")
      (fields (field (name "MANUFACTURER") "Panasonic") (field (name "MPN") "P20283CT-ND"))
      (libsource (lib "eagle-import") (part "1K-ERJ-PB3D1001V"))
    )
    (comp (ref "R117")
      (value "1K")
      (footprint "eagle-import:RC0603N")
      (fields (field (name "MANUFACTURER") "Panasonic") (field (name "MPN") "P20283CT-ND"))
      (libsource (lib "eagle-import") (part "1K-ERJ-PB3D1001V"))
    )
    (comp (ref "R118")
      (value "1K")
      (footprint "eagle-import:RC0603N")
      (fields (field (name "MANUFACTURER") "Panasonic") (field (name "MPN") "P20283CT-ND"))
      (libsource (lib "eagle-import") (part "1K-ERJ-PB3D1001V"))
    )
    (comp (ref "R119")
      (value "1K")
      (footprint "eagle-import:RC0603N")
      (fields (field (name "MANUFACTURER") "Panasonic") (field (name "MPN") "P20283CT-ND"))
      (libsource (lib "eagle-import") (part "1K-ERJ-PB3D1001V"))
    )
    (comp (ref "R120")
      (value "1K")
      (footprint "eagle-import:RC0603N")
      (fields (field (name "MANUFACTURER") "Panasonic") (field (name "MPN") "P20283CT-ND"))
      (libsource (lib "eagle-import") (part "1K-ERJ-PB3D1001V"))
    )
    (comp (ref "R121")
      (value "1K")
      (footprint "eagle-import:RC0603N")
      (fields (field (name "MANUFACTURER") "Panasonic") (field (name "MPN") "P20283CT-ND"))
      (libsource (lib "eagle-import") (part "1K-ERJ-PB3D1001V"))
    )
    (comp (ref "R122")
      (value "1K")
      (footprint "eagle-import:RC0603N")
      (fields (field (name "MANUFACTURER") "Panasonic") (field (name "MPN") "P20283CT-ND"))
      (libsource (lib "eagle-import") (part "1K-ERJ-PB3D1001V"))
    )
    (comp (ref "SJ_A1")
      (value "SOLDERJUMPERREFLOW_NOPASTE")
      (footprint "eagle-import:SJ1")
      (libsource (lib "eagle-import") (part "SOLDERJUMPERREFLOW_NOPASTE"))
    )
    (comp (ref "SJ_A2")
      (value "SOLDERJUMPERREFLOW_NOPASTE")
      (footprint "eagle-import:SJ1")
      (libsource (lib "eagle-import") (part "SOLDERJUMPERREFLOW_NOPASTE"))
    )
    (comp (ref "SJ_A3")
      (value "SOLDERJUMPERREFLOW_NOPASTE")
      (footprint "eagle-import:SJ1")
      (libsource (lib "eagle-import") (part "SOLDERJUMPERREFLOW_NOPASTE"))
    )
    (comp (ref "T3")
      (value "NMOSSOT23")
      (footprint "eagle-import:SOT-23")
      (libsource (lib "eagle-import") (part "NMOSSOT23"))
    )
    (comp (ref "T4")
      (value "NMOSSOT23")
      (footprint "eagle-import:SOT-23")
      (libsource (lib "eagle-import") (part "NMOSSOT23"))
    )
    (comp (ref "TP1")
      (value "TPTP04R")
      (footprint "eagle-import:TP04R")
      (libsource (lib "eagle-import") (part "TPTP04R"))
    )
    (comp (ref "TP2")
      (value "TPTP06R")
      (footprint "eagle-import:TP06R")
      (libsource (lib "eagle-import") (part "TPTP06R"))
    )
    (comp (ref "TP3")
      (value "TPTP04R")
      (footprint "eagle-import:TP04R")
      (libsource (lib "eagle-import") (part "TPTP04R"))
    )
    (comp (ref "TP4")
      (value "TPTP04R")
      (footprint "eagle-import:TP04R")
      (libsource (lib "eagle-import") (part "TPTP04R"))
    )
    (comp (ref "TP5")
      (value "TPTP04R")
      (footprint "eagle-import:TP04R")
      (libsource (lib "eagle-import") (part "TPTP04R"))
    )
    (comp (ref "TP6")
      (value "TPTP04R")
      (footprint "eagle-import:TP04R")
      (libsource (lib "eagle-import") (part "TPTP04R"))
    )
    (comp (ref "TP7")
      (value "TPTP04R")
      (footprint "eagle-import:TP04R")
      (libsource (lib "eagle-import") (part "TPTP04R"))
    )
    (comp (ref "TP104")
      (value "TPTP04R")
      (footprint "eagle-import:TP04R")
      (libsource (lib "eagle-import") (part "TPTP04R"))
    )
    (comp (ref "TP105")
      (value "TPTP04R")
      (footprint "eagle-import:TP04R")
      (libsource (lib "eagle-import") (part "TPTP04R"))
    )
    (comp (ref "U$3")
      (value "PJ-036AH")
      (footprint "eagle-import:BARREL-JACK-PJ-036AH")
      (fields (field (name "MANUFACTURER") "CUI Inc.") (field (name "MPN") "PJ-036AH-SMT-TR"))
      (libsource (lib "eagle-import") (part "BARREL-JACK-PJ-036AH-SMT-TR"))
    )
    (comp (ref "U$5")
      (value "USB_RIGHT")
      (footprint "eagle-import:USB_RIGHT")
      (libsource (lib "eagle-import") (part "USB_RIGHT"))
    )
    (comp (ref "U$6")
      (value "USB_RIGHT")
      (footprint "eagle-import:USB_RIGHT")
      (libsource (lib "eagle-import") (part "USB_RIGHT"))
    )
    (comp (ref "U1")
      (value "TCA9548APWRPW24-M")
      (footprint "eagle-import:PW24-M")
      (fields (field (name "MANUFACTURER_PART_NUMBER") "TCA9548APWR"))
      (libsource (lib "eagle-import") (part "TCA9548APWRPW24-M"))
    )
    (comp (ref "U2")
      (value "RM-3.33.3S")
      (footprint "eagle-import:RM3.33.3S-SIP4")
      (fields (field (name "MANUFACTURER") "Recom Power"))
      (libsource (lib "eagle-import") (part "RM3.33.3S"))
    )
    (comp (ref "U3")
      (value "ISO1540")
      (footprint "eagle-import:D8")
      (fields (field (name "MANUFACTURER") "Texas Instruments") (field (name "MPN") "ISO1540DR"))
      (libsource (lib "eagle-import") (part "ISO1540DR"))
    )
    (comp (ref "U4")
      (value "ISO1540")
      (footprint "eagle-import:D8")
      (fields (field (name "MANUFACTURER") "Texas Instruments") (field (name "MPN") "ISO1540DR"))
      (libsource (lib "eagle-import") (part "ISO1540DR"))
    )
    (comp (ref "U6")
      (value "RM-3.33.3S")
      (footprint "eagle-import:RM3.33.3S-SIP4")
      (fields (field (name "MANUFACTURER") "Recom Power"))
      (libsource (lib "eagle-import") (part "RM3.33.3S"))
    )
    (comp (ref "U8")
      (value "RM-3.33.3S")
      (footprint "eagle-import:RM3.33.3S-SIP4")
      (fields (field (name "MANUFACTURER") "Recom Power"))
      (libsource (lib "eagle-import") (part "RM3.33.3S"))
    )
    (comp (ref "U14")
      (value "ISO1540")
      (footprint "eagle-import:D8")
      (fields (field (name "MANUFACTURER") "Texas Instruments") (field (name "MPN") "ISO1540DR"))
      (libsource (lib "eagle-import") (part "ISO1540DR"))
    )
    (comp (ref "U17")
      (value "LM2937-3.3V")
      (footprint "eagle-import:MP04A")
      (fields (field (name "MANUFACTURER") "Texas Instruments") (field (name "MPN") "LM2937IMP-3.3/NOPB"))
      (libsource (lib "eagle-import") (part "LM2937IMP-3.3/NOPB"))
    )
    (comp (ref "U18")
      (value "DAC5578")
      (footprint "eagle-import:TSSOP16")
      (fields (field (name "MANUFACTURER") "Texas Instruments") (field (name "MPN") "DAC5578SPW"))
      (libsource (lib "eagle-import") (part "DAC5578SPW"))
    )
    (comp (ref "X1")
      (value "MINI-USB-32005-201")
      (footprint "eagle-import:32005-201")
      (libsource (lib "eagle-import") (part "MINI-USB-32005-201"))
    )
    (comp (ref "X2")
      (value "W237-02P")
      (footprint "eagle-import:W237-132")
      (libsource (lib "eagle-import") (part "W237-02P"))
    )
    (comp (ref "X3")
      (value "W237-02P")
      (footprint "eagle-import:W237-132")
      (libsource (lib "eagle-import") (part "W237-02P"))
    )
    (comp (ref "X4")
      (value "22-23-2061")
      (footprint "eagle-import:22-23-2061")
      (fields (field (name "MF") "MOLEX"))
      (libsource (lib "eagle-import") (part "22-23-2061"))
    )
    (comp (ref "X5")
      (value "W237-02P")
      (footprint "eagle-import:W237-132")
      (libsource (lib "eagle-import") (part "W237-02P"))
    )
    (comp (ref "X8")
      (value "W237-02P")
      (footprint "eagle-import:W237-132")
      (libsource (lib "eagle-import") (part "W237-02P"))
    )
  )
  (nets
    (net (code "1") (name "+3V3") (class "Default")
      (node (ref "C10") (pin "1") (pinfunction "1_1") (pintype "passive"))
      (node (ref "C17") (pin "1") (pinfunction "1_1") (pintype "passive"))
      (node (ref "C19") (pin "1") (pinfunction "1_1") (pintype "passive"))
      (node (ref "C2") (pin "1") (pinfunction "1_1") (pintype "passive"))
      (node (ref "C23") (pin "1") (pinfunction "1_1") (pintype "passive"))
      (node (ref "C25") (pin "1") (pinfunction "1_1") (pintype "passive"))
      (node (ref "C26") (pin "1") (pinfunction "1_1") (pintype "passive"))
      (node (ref "C3") (pin "1") (pinfunction "1_1") (pintype "passive"))
      (node (ref "C30") (pin "1") (pinfunction "1_1") (pintype "passive"))
      (node (ref "F1") (pin "2") (pinfunction "2_2") (pintype "passive"))
      (node (ref "JP1") (pin "1") (pinfunction "1_1") (pintype "passive"))
      (node (ref "JP2") (pin "1") (pinfunction "1_1") (pintype "passive"))
      (node (ref "JP3") (pin "1") (pinfunction "1_1") (pintype "passive"))
      (node (ref "JP4") (pin "1") (pinfunction "1_1") (pintype "passive"))
      (node (ref "JP5") (pin "1") (pinfunction "1_1") (pintype "passive"))
      (node (ref "JP6") (pin "1") (pinfunction "1_1") (pintype "passive"))
      (node (ref "JP7") (pin "1") (pinfunction "1_1") (pintype "passive"))
      (node (ref "JP8") (pin "1") (pinfunction "1_1") (pintype "passive"))
      (node (ref "JP9") (pin "1") (pinfunction "1_1") (pintype "passive"))
      (node (ref "R1") (pin "2") (pinfunction "2_2") (pintype "passive"))
      (node (ref "R117") (pin "2") (pinfunction "2_2") (pintype "passive"))
      (node (ref "R118") (pin "2") (pinfunction "2_2") (pintype "passive"))
      (node (ref "R119") (pin "2") (pinfunction "2_2") (pintype "passive"))
      (node (ref "R120") (pin "2") (pinfunction "2_2") (pintype "passive"))
      (node (ref "R121") (pin "2") (pinfunction "2_2") (pintype "passive"))
      (node (ref "R122") (pin "2") (pinfunction "2_2") (pintype "passive"))
      (node (ref "R2") (pin "2") (pinfunction "2_2") (pintype "passive"))
      (node (ref "R33") (pin "2") (pinfunction "2_2") (pintype "passive"))
      (node (ref "R35") (pin "2") (pinfunction "2_2") (pintype "passive"))
      (node (ref "R37") (pin "2") (pinfunction "2_2") (pintype "passive"))
      (node (ref "R39") (pin "2") (pinfunction "2_2") (pintype "passive"))
      (node (ref "R4") (pin "2") (pinfunction "2_2") (pintype "passive"))
      (node (ref "R41") (pin "2") (pinfunction "2_2") (pintype "passive"))
      (node (ref "R42") (pin "2") (pinfunction "2_2") (pintype "passive"))
      (node (ref "R44") (pin "2") (pinfunction "2_2") (pintype "passive"))
      (node (ref "R45") (pin "2") (pinfunction "2_2") (pintype "passive"))
      (node (ref "R47") (pin "2") (pinfunction "2_2") (pintype "passive"))
      (node (ref "R6") (pin "2") (pinfunction "2_2") (pintype "passive"))
      (node (ref "R8") (pin "2") (pinfunction "2_2") (pintype "passive"))
      (node (ref "R88") (pin "1") (pinfunction "1_1") (pintype "passive"))
      (node (ref "R9") (pin "2") (pinfunction "2_2") (pintype "passive"))
      (node (ref "R90") (pin "1") (pinfunction "1_1") (pintype "passive"))
      (node (ref "SJ_A1") (pin "1") (pinfunction "1_1") (pintype "passive"))
      (node (ref "TP2") (pin "TP") (pinfunction "TP_TP") (pintype "input"))
      (node (ref "U1") (pin "24") (pinfunction "VCC_24") (pintype "power_in"))
      (node (ref "U14") (pin "1") (pinfunction "VCC1_1") (pintype "power_in"))
      (node (ref "U18") (pin "3") (pinfunction "AVDD_3") (pintype "bidirectional"))
      (node (ref "U18") (pin "8") (pinfunction "VREF_IN_8") (pintype "bidirectional"))
      (node (ref "U2") (pin "2") (pinfunction "+VIN_2") (pintype "power_in"))
      (node (ref "U3") (pin "1") (pinfunction "VCC1_1") (pintype "power_in"))
      (node (ref "U4") (pin "1") (pinfunction "VCC1_1") (pintype "power_in"))
      (node (ref "U6") (pin "2") (pinfunction "+VIN_2") (pintype "power_in"))
      (node (ref "U8") (pin "2") (pinfunction "+VIN_2") (pintype "power_in"))
      (node (ref "X1") (pin "1") (pinfunction "1_1") (pintype "passive"))
    )
    (net (code "2") (name "+5V") (class "Default")
      (node (ref "C21") (pin "1") (pinfunction "1_1") (pintype "passive"))
      (node (ref "J20") (pin "4") (pinfunction "4_4") (pintype "passive"))
      (node (ref "JP1") (pin "3") (pinfunction "3_3") (pintype "passive"))
      (node (ref "JP2") (pin "3") (pinfunction "3_3") (pintype "passive"))
      (node (ref "JP3") (pin "3") (pinfunction "3_3") (pintype "passive"))
      (node (ref "JP4") (pin "3") (pinfunction "3_3") (pintype "passive"))
      (node (ref "JP5") (pin "3") (pinfunction "3_3") (pintype "passive"))
      (node (ref "JP6") (pin "3") (pinfunction "3_3") (pintype "passive"))
      (node (ref "JP7") (pin "3") (pinfunction "3_3") (pintype "passive"))
      (node (ref "JP8") (pin "3") (pinfunction "3_3") (pintype "passive"))
      (node (ref "JP9") (pin "3") (pinfunction "3_3") (pintype "passive"))
      (node (ref "L1") (pin "OUT+") (pinfunction "OUT+_OUT+") (pintype "bidirectional"))
      (node (ref "R11") (pin "2") (pinfunction "2_2") (pintype "passive"))
      (node (ref "TP3") (pin "1") (pinfunction "TP_1") (pintype "input"))
      (node (ref "U17") (pin "1") (pinfunction "IN_1") (pintype "power_in"))
      (node (ref "X3") (pin "1") (pinfunction "KL_1") (pintype "passive"))
    )
    (net (code "3") (name "+12V") (class "Default")
      (node (ref "L2") (pin "OUT+") (pinfunction "OUT+_OUT+") (pintype "bidirectional"))
      (node (ref "R10") (pin "2") (pinfunction "2_2") (pintype "passive"))
      (node (ref "TP1") (pin "1") (pinfunction "TP_1") (pintype "input"))
      (node (ref "X2") (pin "1") (pinfunction "KL_1") (pintype "passive"))
      (node (ref "X8") (pin "1") (pinfunction "KL_1") (pintype "passive"))
    )
    (net (code "4") (name "+24V") (class "Default")
      (node (ref "F12") (pin "2") (pinfunction "2_2") (pintype "passive"))
      (node (ref "L1") (pin "IN+") (pinfunction "IN+_IN+") (pintype "bidirectional"))
      (node (ref "L2") (pin "IN+") (pinfunction "IN+_IN+") (pintype "bidirectional"))
      (node (ref "R12") (pin "2") (pinfunction "2_2") (pintype "passive"))
      (node (ref "TP4") (pin "1") (pinfunction "TP_1") (pintype "input"))
      (node (ref "X5") (pin "1") (pinfunction "KL_1") (pintype "passive"))
    )
    (net (code "5") (name "/DAC_~{CLR}") (class "Default")
      (node (ref "R88") (pin "2") (pinfunction "2_2") (pintype "passive"))
      (node (ref "TP105") (pin "1") (pinfunction "TP_1") (pintype "input"))
      (node (ref "U18") (pin "9") (pinfunction "~{CLR}_9") (pintype "bidirectional"))
    )
    (net (code "6") (name "/I2C_VCC_1") (class "Default")
      (node (ref "J16") (pin "P$3") (pinfunction "3_P$3") (pintype "bidirectional"))
      (node (ref "JP1") (pin "2") (pinfunction "2_2") (pintype "passive"))
    )
    (net (code "7") (name "/I2C_VCC_2") (class "Default")
      (node (ref "J17") (pin "P$3") (pinfunction "3_P$3") (pintype "bidirectional"))
      (node (ref "JP2") (pin "2") (pinfunction "2_2") (pintype "passive"))
    )
    (net (code "8") (name "/I2C_VCC_3") (class "Default")
      (node (ref "J2") (pin "P$3") (pinfunction "3_P$3") (pintype "bidirectional"))
      (node (ref "JP3") (pin "2") (pinfunction "2_2") (pintype "passive"))
    )
    (net (code "9") (name "/I2C_VCC_4") (class "Default")
      (node (ref "J3") (pin "P$3") (pinfunction "3_P$3") (pintype "bidirectional"))
      (node (ref "JP4") (pin "2") (pinfunction "2_2") (pintype "passive"))
    )
    (net (code "10") (name "/I2C_VCC_5") (class "Default")
      (node (ref "J12") (pin "3") (pinfunction "3_3") (pintype "passive"))
      (node (ref "JP5") (pin "2") (pinfunction "2_2") (pintype "passive"))
    )
    (net (code "11") (name "/I2C_VCC_6") (class "Default")
      (node (ref "J13") (pin "3") (pinfunction "3_3") (pintype "passive"))
      (node (ref "JP6") (pin "2") (pinfunction "2_2") (pintype "passive"))
    )
    (net (code "12") (name "/I2C_VCC_7") (class "Default")
      (node (ref "J14") (pin "3") (pinfunction "3_3") (pintype "passive"))
      (node (ref "JP7") (pin "2") (pinfunction "2_2") (pintype "passive"))
    )
    (net (code "13") (name "/I2C_VCC_8") (class "Default")
      (node (ref "J15") (pin "3") (pinfunction "3_3") (pintype "passive"))
      (node (ref "JP8") (pin "2") (pinfunction "2_2") (pintype "passive"))
    )
    (net (code "14") (name "/VCC_IN_MCP") (class "Default")
      (node (ref "C7") (pin "1") (pinfunction "1_1") (pintype "passive"))
      (node (ref "IC2") (pin "18") (pinfunction "~{RESET}_18") (pintype "input"))
      (node (ref "IC2") (pin "9") (pinfunction "VDD_9") (pintype "power_in"))
      (node (ref "JP9") (pin "2") (pinfunction "2_2") (pintype "passive"))
      (node (ref "R15") (pin "2") (pinfunction "2_2") (pintype "passive"))
      (node (ref "R16") (pin "2") (pinfunction "2_2") (pintype "passive"))
    )
    (net (code "15") (name "/~{LDAC}") (class "Default")
      (node (ref "R90") (pin "2") (pinfunction "2_2") (pintype "passive"))
      (node (ref "SJ_A3") (pin "2") (pinfunction "2_2") (pintype "passive"))
      (node (ref "TP104") (pin "1") (pinfunction "TP_1") (pintype "input"))
      (node (ref "U18") (pin "1") (pinfunction "~{LDAC}_1") (pintype "bidirectional"))
    )
    (net (code "16") (name "24V_IN") (class "Default")
      (node (ref "F12") (pin "1") (pinfunction "1_1") (pintype "passive"))
      (node (ref "U$3") (pin "1") (pinfunction "1_1") (pintype "bidirectional"))
    )
    (net (code "17") (name "A0_EXT_1") (class "Default")
      (node (ref "R4") (pin "1") (pinfunction "1_1") (pintype "passive"))
      (node (ref "R5") (pin "2") (pinfunction "2_2") (pintype "passive"))
      (node (ref "U1") (pin "1") (pinfunction "A0_1") (pintype "input"))
    )
    (net (code "18") (name "A1_EXT_1") (class "Default")
      (node (ref "R6") (pin "1") (pinfunction "1_1") (pintype "passive"))
      (node (ref "R7") (pin "2") (pinfunction "2_2") (pintype "passive"))
      (node (ref "U1") (pin "2") (pinfunction "A1_2") (pintype "input"))
    )
    (net (code "19") (name "A2_EXT_1") (class "Default")
      (node (ref "R2") (pin "1") (pinfunction "1_1") (pintype "passive"))
      (node (ref "R3") (pin "2") (pinfunction "2_2") (pintype "passive"))
      (node (ref "U1") (pin "21") (pinfunction "A2_21") (pintype "input"))
    )
    (net (code "20") (name "ADDR0") (class "Default")
      (node (ref "SJ_A1") (pin "2") (pinfunction "2_2") (pintype "passive"))
      (node (ref "SJ_A2") (pin "2") (pinfunction "2_2") (pintype "passive"))
      (node (ref "U18") (pin "2") (pinfunction "ADDR0_2") (pintype "bidirectional"))
    )
    (net (code "21") (name "D+") (class "Default")
      (node (ref "J7") (pin "2") (pinfunction "2_2") (pintype "passive"))
      (node (ref "U$5") (pin "PIN2") (pinfunction "PIN2_PIN2") (pintype "bidirectional"))
      (node (ref "U$6") (pin "PIN2") (pinfunction "PIN2_PIN2") (pintype "bidirectional"))
    )
    (net (code "22") (name "D-") (class "Default")
      (node (ref "J7") (pin "3") (pinfunction "3_3") (pintype "passive"))
      (node (ref "U$5") (pin "PIN3") (pinfunction "PIN3_PIN3") (pintype "bidirectional"))
      (node (ref "U$6") (pin "PIN3") (pinfunction "PIN3_PIN3") (pintype "bidirectional"))
    )
    (net (code "23") (name "GND") (class "Default")
      (node (ref "D4") (pin "C") (pinfunction "C_C") (pintype "passive"))
      (node (ref "L1") (pin "IN-") (pinfunction "IN-_IN-") (pintype "bidirectional"))
      (node (ref "L2") (pin "IN-") (pinfunction "IN-_IN-") (pintype "bidirectional"))
      (node (ref "TP5") (pin "1") (pinfunction "TP_1") (pintype "input"))
      (node (ref "U$3") (pin "2") (pinfunction "2_2") (pintype "bidirectional"))
      (node (ref "U$3") (pin "3") (pinfunction "3_3") (pintype "bidirectional"))
      (node (ref "X5") (pin "2") (pinfunction "KL_2") (pintype "passive"))
    )
    (net (code "24") (name "GND_(12V)") (class "Default")
      (node (ref "D2") (pin "C") (pinfunction "C_C") (pintype "passive"))
      (node (ref "L2") (pin "OUT-") (pinfunction "OUT-_OUT-") (pintype "bidirectional"))
      (node (ref "TP7") (pin "1") (pinfunction "TP_1") (pintype "input"))
      (node (ref "X2") (pin "2") (pinfunction "KL_2") (pintype "passive"))
      (node (ref "X8") (pin "2") (pinfunction "KL_2") (pintype "passive"))
    )
    (net (code "25") (name "GND_LOGIC") (class "Default")
      (node (ref "C10") (pin "2") (pinfunction "2_2") (pintype "passive"))
      (node (ref "C17") (pin "2") (pinfunction "2_2") (pintype "passive"))
      (node (ref "C19") (pin "2") (pinfunction "2_2") (pintype "passive"))
      (node (ref "C2") (pin "2") (pinfunction "2_2") (pintype "passive"))
      (node (ref "C21") (pin "2") (pinfunction "2_2") (pintype "passive"))
      (node (ref "C22") (pin "2") (pinfunction "2_2") (pintype "passive"))
      (node (ref "C23") (pin "2") (pinfunction "2_2") (pintype "passive"))
      (node (ref "C25") (pin "2") (pinfunction "2_2") (pintype "passive"))
      (node (ref "C26") (pin "2") (pinfunction "2_2") (pintype "passive"))
      (node (ref "C3") (pin "2") (pinfunction "2_2") (pintype "passive"))
      (node (ref "C30") (pin "2") (pinfunction "2_2") (pintype "passive"))
      (node (ref "C7") (pin "2") (pinfunction "2_2") (pintype "passive"))
      (node (ref "D3") (pin "C") (pinfunction "C_C") (pintype "passive"))
      (node (ref "D8") (pin "C") (pinfunction "C_C") (pintype "passive"))
      (node (ref "IC2") (pin "10") (pinfunction "VSS_10") (pintype "power_in"))
      (node (ref "J12") (pin "4") (pinfunction "4_4") (pintype "passive"))
      (node (ref "J13") (pin "4") (pinfunction "4_4") (pintype "passive"))
      (node (ref "J14") (pin "4") (pinfunction "4_4") (pintype "passive"))
      (node (ref "J15") (pin "4") (pinfunction "4_4") (pintype "passive"))
      (node (ref "J16") (pin "P$4") (pinfunction "4_P$4") (pintype "bidirectional"))
      (node (ref "J17") (pin "P$4") (pinfunction "4_P$4") (pintype "bidirectional"))
      (node (ref "J2") (pin "P$4") (pinfunction "4_P$4") (pintype "bidirectional"))
      (node (ref "J20") (pin "3") (pinfunction "3_3") (pintype "passive"))
      (node (ref "J3") (pin "P$4") (pinfunction "4_P$4") (pintype "bidirectional"))
      (node (ref "J7") (pin "4") (pinfunction "4_4") (pintype "passive"))
      (node (ref "J7") (pin "SH1") (pinfunction "SHIELD_SH1") (pintype "passive"))
      (node (ref "J7") (pin "SH2") (pinfunction "SHIELD_SH2") (pintype "passive"))
      (node (ref "L1") (pin "OUT-") (pinfunction "OUT-_OUT-") (pintype "bidirectional"))
      (node (ref "R13") (pin "2") (pinfunction "2_2") (pintype "passive"))
      (node (ref "R3") (pin "1") (pinfunction "1_1") (pintype "passive"))
      (node (ref "R48") (pin "2") (pinfunction "2_2") (pintype "passive"))
      (node (ref "R5") (pin "1") (pinfunction "1_1") (pintype "passive"))
      (node (ref "R7") (pin "1") (pinfunction "1_1") (pintype "passive"))
      (node (ref "SJ_A2") (pin "1") (pinfunction "1_1") (pintype "passive"))
      (node (ref "SJ_A3") (pin "1") (pinfunction "1_1") (pintype "passive"))
      (node (ref "T3") (pin "2") (pinfunction "S_2") (pintype "passive"))
      (node (ref "T4") (pin "2") (pinfunction "S_2") (pintype "passive"))
      (node (ref "TP6") (pin "1") (pinfunction "TP_1") (pintype "input"))
      (node (ref "U$5") (pin "GND1") (pinfunction "CHASIS_GND1") (pintype "bidirectional"))
      (node (ref "U$5") (pin "GND2") (pinfunction "CHASIS_GND2") (pintype "bidirectional"))
      (node (ref "U$5") (pin "GND3") (pinfunction "CHASIS_GND3") (pintype "bidirectional"))
      (node (ref "U$5") (pin "GND4") (pinfunction "CHASIS_GND4") (pintype "bidirectional"))
      (node (ref "U$6") (pin "GND1") (pinfunction "CHASIS_GND1") (pintype "bidirectional"))
      (node (ref "U$6") (pin "GND2") (pinfunction "CHASIS_GND2") (pintype "bidirectional"))
      (node (ref "U$6") (pin "GND3") (pinfunction "CHASIS_GND3") (pintype "bidirectional"))
      (node (ref "U$6") (pin "GND4") (pinfunction "CHASIS_GND4") (pintype "bidirectional"))
      (node (ref "U1") (pin "12") (pinfunction "GND_12") (pintype "power_in"))
      (node (ref "U14") (pin "4") (pinfunction "GND1_4") (pintype "power_in"))
      (node (ref "U17") (pin "2") (pinfunction "GND_2") (pintype "power_in"))
      (node (ref "U17") (pin "4") (pinfunction "TAB_4") (pintype "power_in"))
      (node (ref "U18") (pin "14") (pinfunction "GND_14") (pintype "bidirectional"))
      (node (ref "U2") (pin "1") (pinfunction "-VIN_1") (pintype "power_in"))
      (node (ref "U3") (pin "4") (pinfunction "GND1_4") (pintype "power_in"))
      (node (ref "U4") (pin "4") (pinfunction "GND1_4") (pintype "power_in"))
      (node (ref "U6") (pin "1") (pinfunction "-VIN_1") (pintype "power_in"))
      (node (ref "U8") (pin "1") (pinfunction "-VIN_1") (pintype "power_in"))
      (node (ref "X1") (pin "4") (pinfunction "4_4") (pintype "passive"))
      (node (ref "X1") (pin "5") (pinfunction "5_5") (pintype "passive"))
      (node (ref "X3") (pin "2") (pinfunction "KL_2") (pintype "passive"))
    )
    (net (code "26") (name "ISO_3V3_2") (class "Default")
      (node (ref "C12") (pin "1") (pinfunction "1_1") (pintype "passive"))
      (node (ref "C4") (pin "1") (pinfunction "1_1") (pintype "passive"))
      (node (ref "J9") (pin "4") (pinfunction "VCC_4") (pintype "power_in"))
      (node (ref "R34") (pin "2") (pinfunction "2_2") (pintype "passive"))
      (node (ref "R36") (pin "2") (pinfunction "2_2") (pintype "passive"))
      (node (ref "U2") (pin "4") (pinfunction "+VOUT_4") (pintype "power_in"))
      (node (ref "U3") (pin "8") (pinfunction "ISO_VCC2_8") (pintype "power_in"))
    )
    (net (code "27") (name "ISO_3V3_3") (class "Default")
      (node (ref "C18") (pin "1") (pinfunction "1_1") (pintype "passive"))
      (node (ref "C20") (pin "1") (pinfunction "1_1") (pintype "passive"))
      (node (ref "J10") (pin "4") (pinfunction "VCC_4") (pintype "power_in"))
      (node (ref "R38") (pin "2") (pinfunction "2_2") (pintype "passive"))
      (node (ref "R40") (pin "2") (pinfunction "2_2") (pintype "passive"))
      (node (ref "U4") (pin "8") (pinfunction "ISO_VCC2_8") (pintype "power_in"))
      (node (ref "U6") (pin "4") (pinfunction "+VOUT_4") (pintype "power_in"))
    )
    (net (code "28") (name "ISO_3V3_4") (class "Default")
      (node (ref "C24") (pin "1") (pinfunction "1_1") (pintype "passive"))
      (node (ref "C27") (pin "1") (pinfunction "1_1") (pintype "passive"))
      (node (ref "J8") (pin "4") (pinfunction "VCC_4") (pintype "power_in"))
      (node (ref "R43") (pin "2") (pinfunction "2_2") (pintype "passive"))
      (node (ref "R46") (pin "2") (pinfunction "2_2") (pintype "passive"))
      (node (ref "U14") (pin "8") (pinfunction "ISO_VCC2_8") (pintype "power_in"))
      (node (ref "U8") (pin "4") (pinfunction "+VOUT_4") (pintype "power_in"))
    )
    (net (code "29") (name "ISO_GND_2") (class "Default")
      (node (ref "C12") (pin "2") (pinfunction "2_2") (pintype "passive"))
      (node (ref "C4") (pin "2") (pinfunction "2_2") (pintype "passive"))
      (node (ref "J9") (pin "3") (pinfunction "GND_3") (pintype "power_in"))
      (node (ref "U2") (pin "3") (pinfunction "-VOUT_3") (pintype "power_in"))
      (node (ref "U3") (pin "5") (pinfunction "ISO_GND2_5") (pintype "power_in"))
    )
    (net (code "30") (name "ISO_GND_3") (class "Default")
      (node (ref "C18") (pin "2") (pinfunction "2_2") (pintype "passive"))
      (node (ref "C20") (pin "2") (pinfunction "2_2") (pintype "passive"))
      (node (ref "J10") (pin "3") (pinfunction "GND_3") (pintype "power_in"))
      (node (ref "U4") (pin "5") (pinfunction "ISO_GND2_5") (pintype "power_in"))
      (node (ref "U6") (pin "3") (pinfunction "-VOUT_3") (pintype "power_in"))
    )
    (net (code "31") (name "ISO_GND_4") (class "Default")
      (node (ref "C24") (pin "2") (pinfunction "2_2") (pintype "passive"))
      (node (ref "C27") (pin "2") (pinfunction "2_2") (pintype "passive"))
      (node (ref "J8") (pin "3") (pinfunction "GND_3") (pintype "power_in"))
      (node (ref "U14") (pin "5") (pinfunction "ISO_GND2_5") (pintype "power_in"))
      (node (ref "U8") (pin "3") (pinfunction "-VOUT_3") (pintype "power_in"))
    )
    (net (code "32") (name "ISO_SCL_2") (class "Default")
      (node (ref "J9") (pin "1") (pinfunction "RX/SCL_1") (pintype "bidirectional"))
      (node (ref "R36") (pin "1") (pinfunction "1_1") (pintype "passive"))
      (node (ref "U3") (pin "6") (pinfunction "ISO_SCL2_6") (pintype "bidirectional"))
    )
    (net (code "33") (name "ISO_SCL_3") (class "Default")
      (node (ref "J10") (pin "1") (pinfunction "RX/SCL_1") (pintype "bidirectional"))
      (node (ref "R40") (pin "1") (pinfunction "1_1") (pintype "passive"))
      (node (ref "U4") (pin "6") (pinfunction "ISO_SCL2_6") (pintype "bidirectional"))
    )
    (net (code "34") (name "ISO_SCL_4") (class "Default")
      (node (ref "J8") (pin "1") (pinfunction "RX/SCL_1") (pintype "bidirectional"))
      (node (ref "R46") (pin "1") (pinfunction "1_1") (pintype "passive"))
      (node (ref "U14") (pin "6") (pinfunction "ISO_SCL2_6") (pintype "bidirectional"))
    )
    (net (code "35") (name "ISO_SDA_2") (class "Default")
      (node (ref "J9") (pin "2") (pinfunction "TX/SDA_2") (pintype "bidirectional"))
      (node (ref "R34") (pin "1") (pinfunction "1_1") (pintype "passive"))
      (node (ref "U3") (pin "7") (pinfunction "ISO_SDA2_7") (pintype "bidirectional"))
    )
    (net (code "36") (name "ISO_SDA_3") (class "Default")
      (node (ref "J10") (pin "2") (pinfunction "TX/SDA_2") (pintype "bidirectional"))
      (node (ref "R38") (pin "1") (pinfunction "1_1") (pintype "passive"))
      (node (ref "U4") (pin "7") (pinfunction "ISO_SDA2_7") (pintype "bidirectional"))
    )
    (net (code "37") (name "ISO_SDA_4") (class "Default")
      (node (ref "J8") (pin "2") (pinfunction "TX/SDA_2") (pintype "bidirectional"))
      (node (ref "R43") (pin "1") (pinfunction "1_1") (pintype "passive"))
      (node (ref "U14") (pin "7") (pinfunction "ISO_SDA2_7") (pintype "bidirectional"))
    )
    (net (code "38") (name "Net-(D2-PadA)") (class "Default")
      (node (ref "D2") (pin "A") (pinfunction "A_A") (pintype "passive"))
      (node (ref "R10") (pin "1") (pinfunction "1_1") (pintype "passive"))
    )
    (net (code "39") (name "Net-(D3-PadA)") (class "Default")
      (node (ref "D3") (pin "A") (pinfunction "A_A") (pintype "passive"))
      (node (ref "R11") (pin "1") (pinfunction "1_1") (pintype "passive"))
    )
    (net (code "40") (name "Net-(D4-PadA)") (class "Default")
      (node (ref "D4") (pin "A") (pinfunction "A_A") (pintype "passive"))
      (node (ref "R12") (pin "1") (pinfunction "1_1") (pintype "passive"))
    )
    (net (code "41") (name "Net-(D8-PadA)") (class "Default")
      (node (ref "D8") (pin "A") (pinfunction "A_A") (pintype "passive"))
      (node (ref "R44") (pin "1") (pinfunction "1_1") (pintype "passive"))
    )
    (net (code "42") (name "Net-(IC2-GPA0)") (class "Default")
      (node (ref "IC2") (pin "21") (pinfunction "GPA0_21") (pintype "bidirectional"))
      (node (ref "R17") (pin "2") (pinfunction "2_2") (pintype "passive"))
    )
    (net (code "43") (name "Net-(IC2-GPA1)") (class "Default")
      (node (ref "IC2") (pin "22") (pinfunction "GPA1_22") (pintype "bidirectional"))
      (node (ref "R18") (pin "2") (pinfunction "2_2") (pintype "passive"))
    )
    (net (code "44") (name "Net-(IC2-GPA2)") (class "Default")
      (node (ref "IC2") (pin "23") (pinfunction "GPA2_23") (pintype "bidirectional"))
      (node (ref "R19") (pin "2") (pinfunction "2_2") (pintype "passive"))
    )
    (net (code "45") (name "Net-(IC2-GPA3)") (class "Default")
      (node (ref "IC2") (pin "24") (pinfunction "GPA3_24") (pintype "bidirectional"))
      (node (ref "R20") (pin "2") (pinfunction "2_2") (pintype "passive"))
    )
    (net (code "46") (name "Net-(IC2-GPA4)") (class "Default")
      (node (ref "IC2") (pin "25") (pinfunction "GPA4_25") (pintype "bidirectional"))
      (node (ref "R21") (pin "2") (pinfunction "2_2") (pintype "passive"))
    )
    (net (code "47") (name "Net-(IC2-GPA5)") (class "Default")
      (node (ref "IC2") (pin "26") (pinfunction "GPA5_26") (pintype "bidirectional"))
      (node (ref "R22") (pin "2") (pinfunction "2_2") (pintype "passive"))
    )
    (net (code "48") (name "Net-(IC2-GPA6)") (class "Default")
      (node (ref "IC2") (pin "27") (pinfunction "GPA6_27") (pintype "bidirectional"))
      (node (ref "R23") (pin "2") (pinfunction "2_2") (pintype "passive"))
    )
    (net (code "49") (name "Net-(IC2-GPA7)") (class "Default")
      (node (ref "IC2") (pin "28") (pinfunction "GPA7_28") (pintype "bidirectional"))
      (node (ref "R24") (pin "2") (pinfunction "2_2") (pintype "passive"))
    )
    (net (code "50") (name "Net-(IC2-GPB0)") (class "Default")
      (node (ref "IC2") (pin "1") (pinfunction "GPB0_1") (pintype "bidirectional"))
      (node (ref "R32") (pin "1") (pinfunction "1_1") (pintype "passive"))
    )
    (net (code "51") (name "Net-(IC2-GPB1)") (class "Default")
      (node (ref "IC2") (pin "2") (pinfunction "GPB1_2") (pintype "bidirectional"))
      (node (ref "R31") (pin "1") (pinfunction "1_1") (pintype "passive"))
    )
    (net (code "52") (name "Net-(IC2-GPB2)") (class "Default")
      (node (ref "IC2") (pin "3") (pinfunction "GPB2_3") (pintype "bidirectional"))
      (node (ref "R30") (pin "1") (pinfunction "1_1") (pintype "passive"))
    )
    (net (code "53") (name "Net-(IC2-GPB3)") (class "Default")
      (node (ref "IC2") (pin "4") (pinfunction "GPB3_4") (pintype "bidirectional"))
      (node (ref "R29") (pin "1") (pinfunction "1_1") (pintype "passive"))
    )
    (net (code "54") (name "Net-(IC2-GPB4)") (class "Default")
      (node (ref "IC2") (pin "5") (pinfunction "GPB4_5") (pintype "bidirectional"))
      (node (ref "R28") (pin "1") (pinfunction "1_1") (pintype "passive"))
    )
    (net (code "55") (name "Net-(IC2-GPB5)") (class "Default")
      (node (ref "IC2") (pin "6") (pinfunction "GPB5_6") (pintype "bidirectional"))
      (node (ref "R27") (pin "1") (pinfunction "1_1") (pintype "passive"))
    )
    (net (code "56") (name "Net-(IC2-GPB6)") (class "Default")
      (node (ref "IC2") (pin "7") (pinfunction "GPB6_7") (pintype "bidirectional"))
      (node (ref "R26") (pin "1") (pinfunction "1_1") (pintype "passive"))
    )
    (net (code "57") (name "Net-(IC2-GPB7)") (class "Default")
      (node (ref "IC2") (pin "8") (pinfunction "GPB7_8") (pintype "bidirectional"))
      (node (ref "R25") (pin "1") (pinfunction "1_1") (pintype "passive"))
    )
    (net (code "58") (name "Net-(J18-Pad1)") (class "Default")
      (node (ref "J18") (pin "1") (pinfunction "1_1") (pintype "passive"))
      (node (ref "R17") (pin "1") (pinfunction "1_1") (pintype "passive"))
    )
    (net (code "59") (name "Net-(J18-Pad2)") (class "Default")
      (node (ref "J18") (pin "2") (pinfunction "2_2") (pintype "passive"))
      (node (ref "R18") (pin "1") (pinfunction "1_1") (pintype "passive"))
    )
    (net (code "60") (name "Net-(J18-Pad3)") (class "Default")
      (node (ref "J18") (pin "3") (pinfunction "3_3") (pintype "passive"))
      (node (ref "R19") (pin "1") (pinfunction "1_1") (pintype "passive"))
    )
    (net (code "61") (name "Net-(J18-Pad4)") (class "Default")
      (node (ref "J18") (pin "4") (pinfunction "4_4") (pintype "passive"))
      (node (ref "R20") (pin "1") (pinfunction "1_1") (pintype "passive"))
    )
    (net (code "62") (name "Net-(J18-Pad5)") (class "Default")
      (node (ref "J18") (pin "5") (pinfunction "5_5") (pintype "passive"))
      (node (ref "R21") (pin "1") (pinfunction "1_1") (pintype "passive"))
    )
    (net (code "63") (name "Net-(J18-Pad6)") (class "Default")
      (node (ref "J18") (pin "6") (pinfunction "6_6") (pintype "passive"))
      (node (ref "R22") (pin "1") (pinfunction "1_1") (pintype "passive"))
    )
    (net (code "64") (name "Net-(J18-Pad7)") (class "Default")
      (node (ref "J18") (pin "7") (pinfunction "7_7") (pintype "passive"))
      (node (ref "R23") (pin "1") (pinfunction "1_1") (pintype "passive"))
    )
    (net (code "65") (name "Net-(J18-Pad8)") (class "Default")
      (node (ref "J18") (pin "8") (pinfunction "8_8") (pintype "passive"))
      (node (ref "R24") (pin "1") (pinfunction "1_1") (pintype "passive"))
    )
    (net (code "66") (name "Net-(J19-Pad1)") (class "Default")
      (node (ref "J19") (pin "1") (pinfunction "1_1") (pintype "passive"))
      (node (ref "R32") (pin "2") (pinfunction "2_2") (pintype "passive"))
    )
    (net (code "67") (name "Net-(J19-Pad2)") (class "Default")
      (node (ref "J19") (pin "2") (pinfunction "2_2") (pintype "passive"))
      (node (ref "R31") (pin "2") (pinfunction "2_2") (pintype "passive"))
    )
    (net (code "68") (name "Net-(J19-Pad3)") (class "Default")
      (node (ref "J19") (pin "3") (pinfunction "3_3") (pintype "passive"))
      (node (ref "R30") (pin "2") (pinfunction "2_2") (pintype "passive"))
    )
    (net (code "69") (name "Net-(J19-Pad4)") (class "Default")
      (node (ref "J19") (pin "4") (pinfunction "4_4") (pintype "passive"))
      (node (ref "R29") (pin "2") (pinfunction "2_2") (pintype "passive"))
    )
    (net (code "70") (name "Net-(J19-Pad5)") (class "Default")
      (node (ref "J19") (pin "5") (pinfunction "5_5") (pintype "passive"))
      (node (ref "R28") (pin "2") (pinfunction "2_2") (pintype "passive"))
    )
    (net (code "71") (name "Net-(J19-Pad6)") (class "Default")
      (node (ref "J19") (pin "6") (pinfunction "6_6") (pintype "passive"))
      (node (ref "R27") (pin "2") (pinfunction "2_2") (pintype "passive"))
    )
    (net (code "72") (name "Net-(J19-Pad7)") (class "Default")
      (node (ref "J19") (pin "7") (pinfunction "7_7") (pintype "passive"))
      (node (ref "R26") (pin "2") (pinfunction "2_2") (pintype "passive"))
    )
    (net (code "73") (name "Net-(J19-Pad8)") (class "Default")
      (node (ref "J19") (pin "8") (pinfunction "8_8") (pintype "passive"))
      (node (ref "R25") (pin "2") (pinfunction "2_2") (pintype "passive"))
    )
    (net (code "74") (name "Net-(T3-D)") (class "Default")
      (node (ref "T3") (pin "1") (pinfunction "D_1") (pintype "passive"))
      (node (ref "U$6") (pin "PIN4") (pinfunction "PIN4_PIN4") (pintype "bidirectional"))
    )
    (net (code "75") (name "Net-(T3-G)") (class "Default")
      (node (ref "R48") (pin "1") (pinfunction "1_1") (pintype "passive"))
      (node (ref "R49") (pin "1") (pinfunction "1_1") (pintype "passive"))
      (node (ref "T3") (pin "3") (pinfunction "G_3") (pintype "passive"))
    )
    (net (code "76") (name "Net-(T4-D)") (class "Default")
      (node (ref "T4") (pin "1") (pinfunction "D_1") (pintype "passive"))
      (node (ref "U$5") (pin "PIN4") (pinfunction "PIN4_PIN4") (pintype "bidirectional"))
    )
    (net (code "77") (name "Net-(T4-G)") (class "Default")
      (node (ref "R13") (pin "1") (pinfunction "1_1") (pintype "passive"))
      (node (ref "R14") (pin "1") (pinfunction "1_1") (pintype "passive"))
      (node (ref "T4") (pin "3") (pinfunction "G_3") (pintype "passive"))
    )
    (net (code "78") (name "Net-(U17-OUT)") (class "Default")
      (node (ref "C22") (pin "1") (pinfunction "1_1") (pintype "passive"))
      (node (ref "F1") (pin "1") (pinfunction "1_1") (pintype "passive"))
      (node (ref "U17") (pin "3") (pinfunction "OUT_3") (pintype "power_in"))
    )
    (net (code "79") (name "PGND_2") (class "Default")
      (node (ref "J1") (pin "2") (pinfunction "2_2") (pintype "passive"))
      (node (ref "J1") (pin "3") (pinfunction "3_3") (pintype "passive"))
      (node (ref "J1") (pin "4") (pinfunction "4_4") (pintype "passive"))
      (node (ref "J1") (pin "5") (pinfunction "5_5") (pintype "passive"))
      (node (ref "J9") (pin "6") (pinfunction "PGND_6") (pintype "power_in"))
    )
    (net (code "80") (name "PGND_3") (class "Default")
      (node (ref "J10") (pin "6") (pinfunction "PGND_6") (pintype "power_in"))
      (node (ref "J6") (pin "2") (pinfunction "2_2") (pintype "passive"))
      (node (ref "J6") (pin "3") (pinfunction "3_3") (pintype "passive"))
      (node (ref "J6") (pin "4") (pinfunction "4_4") (pintype "passive"))
      (node (ref "J6") (pin "5") (pinfunction "5_5") (pintype "passive"))
    )
    (net (code "81") (name "PGND_4") (class "Default")
      (node (ref "J5") (pin "2") (pinfunction "2_2") (pintype "passive"))
      (node (ref "J5") (pin "3") (pinfunction "3_3") (pintype "passive"))
      (node (ref "J5") (pin "4") (pinfunction "4_4") (pintype "passive"))
      (node (ref "J5") (pin "5") (pinfunction "5_5") (pintype "passive"))
      (node (ref "J8") (pin "6") (pinfunction "PGND_6") (pintype "power_in"))
    )
    (net (code "82") (name "PRB_2") (class "Default")
      (node (ref "J1") (pin "1") (pinfunction "1_1") (pintype "passive"))
      (node (ref "J9") (pin "5") (pinfunction "PBR_5") (pintype "bidirectional"))
    )
    (net (code "83") (name "PRB_3") (class "Default")
      (node (ref "J10") (pin "5") (pinfunction "PBR_5") (pintype "bidirectional"))
      (node (ref "J6") (pin "1") (pinfunction "1_1") (pintype "passive"))
    )
    (net (code "84") (name "PRB_4") (class "Default")
      (node (ref "J5") (pin "1") (pinfunction "1_1") (pintype "passive"))
      (node (ref "J8") (pin "5") (pinfunction "PBR_5") (pintype "bidirectional"))
    )
    (net (code "85") (name "RESET1") (class "Default")
      (node (ref "R1") (pin "1") (pinfunction "1_1") (pintype "passive"))
      (node (ref "U1") (pin "3") (pinfunction "~{RESET}_3") (pintype "input"))
    )
    (net (code "86") (name "SC0") (class "Default")
      (node (ref "U1") (pin "5") (pinfunction "SC0_5") (pintype "passive"))
    )
    (net (code "87") (name "SC1") (class "Default")
      (node (ref "IC2") (pin "12") (pinfunction "SCL_12") (pintype "input"))
      (node (ref "R16") (pin "1") (pinfunction "1_1") (pintype "passive"))
      (node (ref "U1") (pin "7") (pinfunction "SC1_7") (pintype "passive"))
    )
    (net (code "88") (name "SC2") (class "Default")
      (node (ref "R47") (pin "1") (pinfunction "1_1") (pintype "passive"))
      (node (ref "U1") (pin "9") (pinfunction "SC2_9") (pintype "passive"))
      (node (ref "X1") (pin "3") (pinfunction "3_3") (pintype "passive"))
    )
    (net (code "89") (name "SC3") (class "Default")
      (node (ref "U1") (pin "11") (pinfunction "SC3_11") (pintype "passive"))
      (node (ref "U18") (pin "16") (pinfunction "SCL_16") (pintype "bidirectional"))
    )
    (net (code "90") (name "SC4") (class "Default")
      (node (ref "U1") (pin "14") (pinfunction "SC4_14") (pintype "passive"))
    )
    (net (code "91") (name "SC5") (class "Default")
      (node (ref "J12") (pin "1") (pinfunction "1_1") (pintype "passive"))
      (node (ref "J13") (pin "1") (pinfunction "1_1") (pintype "passive"))
      (node (ref "J14") (pin "1") (pinfunction "1_1") (pintype "passive"))
      (node (ref "J15") (pin "1") (pinfunction "1_1") (pintype "passive"))
      (node (ref "U1") (pin "16") (pinfunction "SC5_16") (pintype "passive"))
    )
    (net (code "92") (name "SC6") (class "Default")
      (node (ref "R33") (pin "1") (pinfunction "1_1") (pintype "passive"))
      (node (ref "R37") (pin "1") (pinfunction "1_1") (pintype "passive"))
      (node (ref "R41") (pin "1") (pinfunction "1_1") (pintype "passive"))
      (node (ref "U1") (pin "18") (pinfunction "SC6_18") (pintype "passive"))
      (node (ref "U14") (pin "3") (pinfunction "SCL1_3") (pintype "bidirectional"))
      (node (ref "U3") (pin "3") (pinfunction "SCL1_3") (pintype "bidirectional"))
      (node (ref "U4") (pin "3") (pinfunction "SCL1_3") (pintype "bidirectional"))
    )
    (net (code "93") (name "SC7") (class "Default")
      (node (ref "J16") (pin "P$1") (pinfunction "1_P$1") (pintype "bidirectional"))
      (node (ref "J17") (pin "P$1") (pinfunction "1_P$1") (pintype "bidirectional"))
      (node (ref "J2") (pin "P$1") (pinfunction "1_P$1") (pintype "bidirectional"))
      (node (ref "J3") (pin "P$1") (pinfunction "1_P$1") (pintype "bidirectional"))
      (node (ref "U1") (pin "20") (pinfunction "SC7_20") (pintype "passive"))
    )
    (net (code "94") (name "SCL") (class "Default")
      (node (ref "J20") (pin "1") (pinfunction "1_1") (pintype "passive"))
      (node (ref "R8") (pin "1") (pinfunction "1_1") (pintype "passive"))
      (node (ref "U1") (pin "22") (pinfunction "SCL_22") (pintype "passive"))
    )
    (net (code "95") (name "SD0") (class "Default")
      (node (ref "U1") (pin "4") (pinfunction "SD0_4") (pintype "passive"))
    )
    (net (code "96") (name "SD1") (class "Default")
      (node (ref "IC2") (pin "13") (pinfunction "SDA_13") (pintype "bidirectional"))
      (node (ref "R15") (pin "1") (pinfunction "1_1") (pintype "passive"))
      (node (ref "U1") (pin "6") (pinfunction "SD1_6") (pintype "passive"))
    )
    (net (code "97") (name "SD2") (class "Default")
      (node (ref "R42") (pin "1") (pinfunction "1_1") (pintype "passive"))
      (node (ref "U1") (pin "8") (pinfunction "SD2_8") (pintype "passive"))
      (node (ref "X1") (pin "2") (pinfunction "2_2") (pintype "passive"))
    )
    (net (code "98") (name "SD3") (class "Default")
      (node (ref "U1") (pin "10") (pinfunction "SD3_10") (pintype "passive"))
      (node (ref "U18") (pin "15") (pinfunction "SDA_15") (pintype "bidirectional"))
    )
    (net (code "99") (name "SD4") (class "Default")
      (node (ref "U1") (pin "13") (pinfunction "SD4_13") (pintype "passive"))
    )
    (net (code "100") (name "SD5") (class "Default")
      (node (ref "J12") (pin "2") (pinfunction "2_2") (pintype "passive"))
      (node (ref "J13") (pin "2") (pinfunction "2_2") (pintype "passive"))
      (node (ref "J14") (pin "2") (pinfunction "2_2") (pintype "passive"))
      (node (ref "J15") (pin "2") (pinfunction "2_2") (pintype "passive"))
      (node (ref "U1") (pin "15") (pinfunction "SD5_15") (pintype "passive"))
    )
    (net (code "101") (name "SD6") (class "Default")
      (node (ref "R35") (pin "1") (pinfunction "1_1") (pintype "passive"))
      (node (ref "R39") (pin "1") (pinfunction "1_1") (pintype "passive"))
      (node (ref "R45") (pin "1") (pinfunction "1_1") (pintype "passive"))
      (node (ref "U1") (pin "17") (pinfunction "SD6_17") (pintype "passive"))
      (node (ref "U14") (pin "2") (pinfunction "SDA1_2") (pintype "bidirectional"))
      (node (ref "U3") (pin "2") (pinfunction "SDA1_2") (pintype "bidirectional"))
      (node (ref "U4") (pin "2") (pinfunction "SDA1_2") (pintype "bidirectional"))
    )
    (net (code "102") (name "SD7") (class "Default")
      (node (ref "J16") (pin "P$2") (pinfunction "2_P$2") (pintype "bidirectional"))
      (node (ref "J17") (pin "P$2") (pinfunction "2_P$2") (pintype "bidirectional"))
      (node (ref "J2") (pin "P$2") (pinfunction "2_P$2") (pintype "bidirectional"))
      (node (ref "J3") (pin "P$2") (pinfunction "2_P$2") (pintype "bidirectional"))
      (node (ref "U1") (pin "19") (pinfunction "SD7_19") (pintype "passive"))
    )
    (net (code "103") (name "SDA") (class "Default")
      (node (ref "J20") (pin "2") (pinfunction "2_2") (pintype "passive"))
      (node (ref "R9") (pin "1") (pinfunction "1_1") (pintype "passive"))
      (node (ref "U1") (pin "23") (pinfunction "SDA_23") (pintype "passive"))
    )
    (net (code "104") (name "USB1") (class "Default")
      (node (ref "R49") (pin "2") (pinfunction "2_2") (pintype "passive"))
      (node (ref "U18") (pin "12") (pinfunction "VOUT_D_12") (pintype "bidirectional"))
    )
    (net (code "105") (name "USB2") (class "Default")
      (node (ref "R14") (pin "2") (pinfunction "2_2") (pintype "passive"))
      (node (ref "U18") (pin "13") (pinfunction "VOUT_B_13") (pintype "bidirectional"))
    )
    (net (code "106") (name "V+") (class "Default")
      (node (ref "J7") (pin "1") (pinfunction "1_1") (pintype "passive"))
      (node (ref "U$5") (pin "PIN1") (pinfunction "PIN1_PIN1") (pintype "bidirectional"))
      (node (ref "U$6") (pin "PIN1") (pinfunction "PIN1_PIN1") (pintype "bidirectional"))
    )
    (net (code "107") (name "VSET") (class "Default")
      (node (ref "R117") (pin "1") (pinfunction "1_1") (pintype "passive"))
      (node (ref "U18") (pin "7") (pinfunction "VOUT_G_7") (pintype "bidirectional"))
      (node (ref "X4") (pin "1") (pinfunction "S_1") (pintype "passive"))
    )
    (net (code "108") (name "VSET_2") (class "Default")
      (node (ref "R118") (pin "1") (pinfunction "1_1") (pintype "passive"))
      (node (ref "U18") (pin "6") (pinfunction "VOUT_E_6") (pintype "bidirectional"))
      (node (ref "X4") (pin "2") (pinfunction "S_2") (pintype "passive"))
    )
    (net (code "109") (name "VSET_3") (class "Default")
      (node (ref "R119") (pin "1") (pinfunction "1_1") (pintype "passive"))
      (node (ref "U18") (pin "5") (pinfunction "VOUT_C_5") (pintype "bidirectional"))
      (node (ref "X4") (pin "3") (pinfunction "S_3") (pintype "passive"))
    )
    (net (code "110") (name "VSET_4") (class "Default")
      (node (ref "R120") (pin "1") (pinfunction "1_1") (pintype "passive"))
      (node (ref "U18") (pin "4") (pinfunction "VOUT_A_4") (pintype "bidirectional"))
      (node (ref "X4") (pin "4") (pinfunction "S_4") (pintype "passive"))
    )
    (net (code "111") (name "VSET_5") (class "Default")
      (node (ref "R121") (pin "1") (pinfunction "1_1") (pintype "passive"))
      (node (ref "U18") (pin "10") (pinfunction "VOUT_H_10") (pintype "bidirectional"))
      (node (ref "X4") (pin "5") (pinfunction "S_5") (pintype "passive"))
    )
    (net (code "112") (name "VSET_6") (class "Default")
      (node (ref "R122") (pin "1") (pinfunction "1_1") (pintype "passive"))
      (node (ref "U18") (pin "11") (pinfunction "VOUT_F_11") (pintype "bidirectional"))
      (node (ref "X4") (pin "6") (pinfunction "S_6") (pintype "passive"))
    )
    (net (code "113") (name "unconnected-(IC2-A0-Pad15)") (class "Default")
      (node (ref "IC2") (pin "15") (pinfunction "A0_15") (pintype "input"))
    )
    (net (code "114") (name "unconnected-(IC2-A1-Pad16)") (class "Default")
      (node (ref "IC2") (pin "16") (pinfunction "A1_16") (pintype "input"))
    )
    (net (code "115") (name "unconnected-(IC2-A2-Pad17)") (class "Default")
      (node (ref "IC2") (pin "17") (pinfunction "A2_17") (pintype "input"))
    )
    (net (code "116") (name "unconnected-(IC2-INTA-Pad20)") (class "Default")
      (node (ref "IC2") (pin "20") (pinfunction "INTA_20") (pintype "output"))
    )
    (net (code "117") (name "unconnected-(IC2-INTB-Pad19)") (class "Default")
      (node (ref "IC2") (pin "19") (pinfunction "INTB_19") (pintype "output"))
    )
  )
)
